# MainControl20V032.net
KiCad netlist of a schematic drawn in Altium Designer
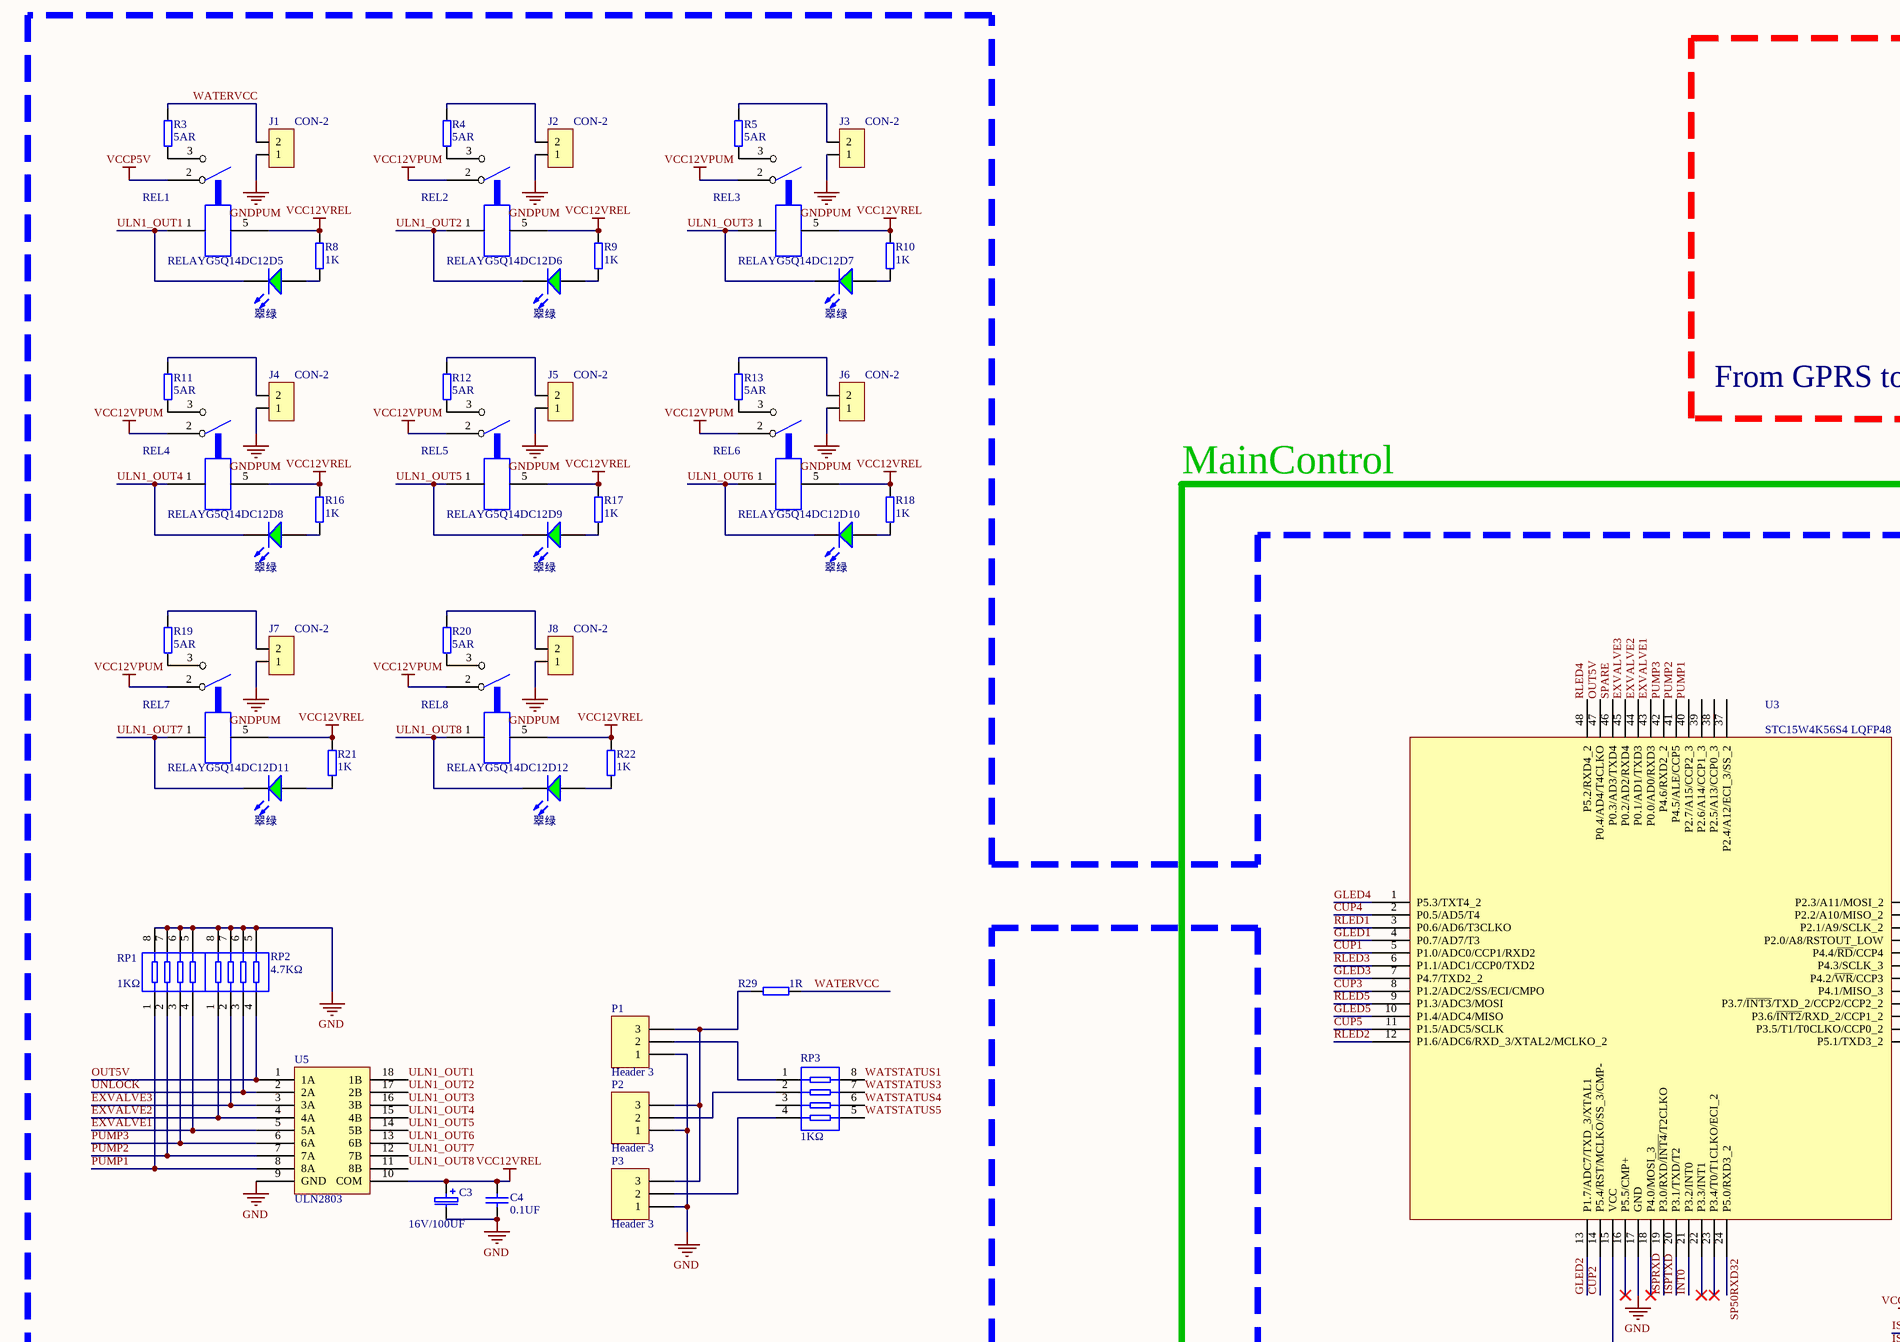
[diagram p0: MainControl20V032.SchDoc, top left]
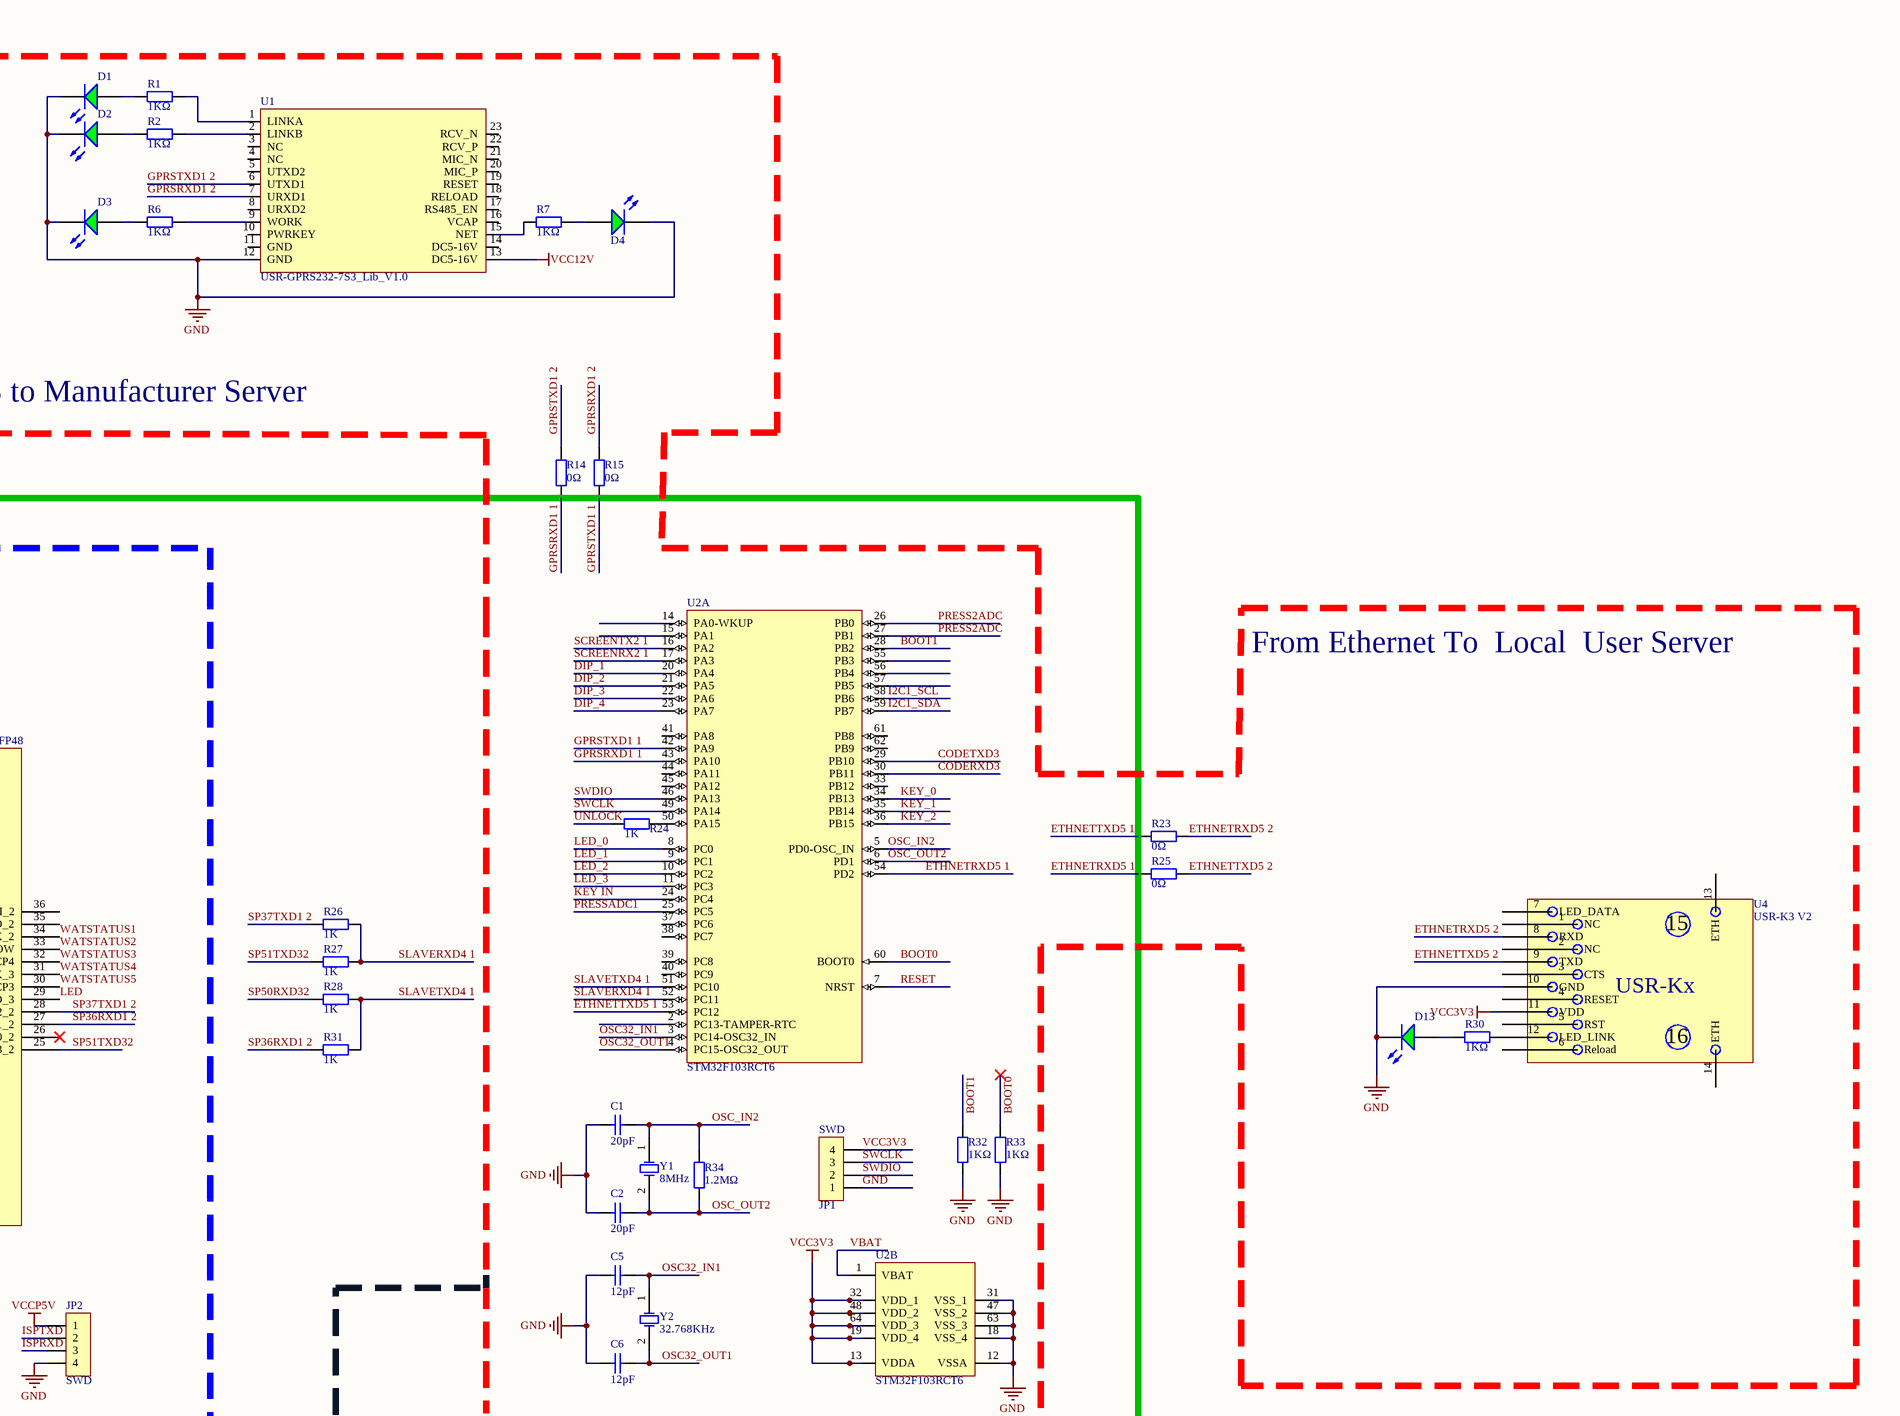
[diagram p1: MainControl20V032.SchDoc, top right]
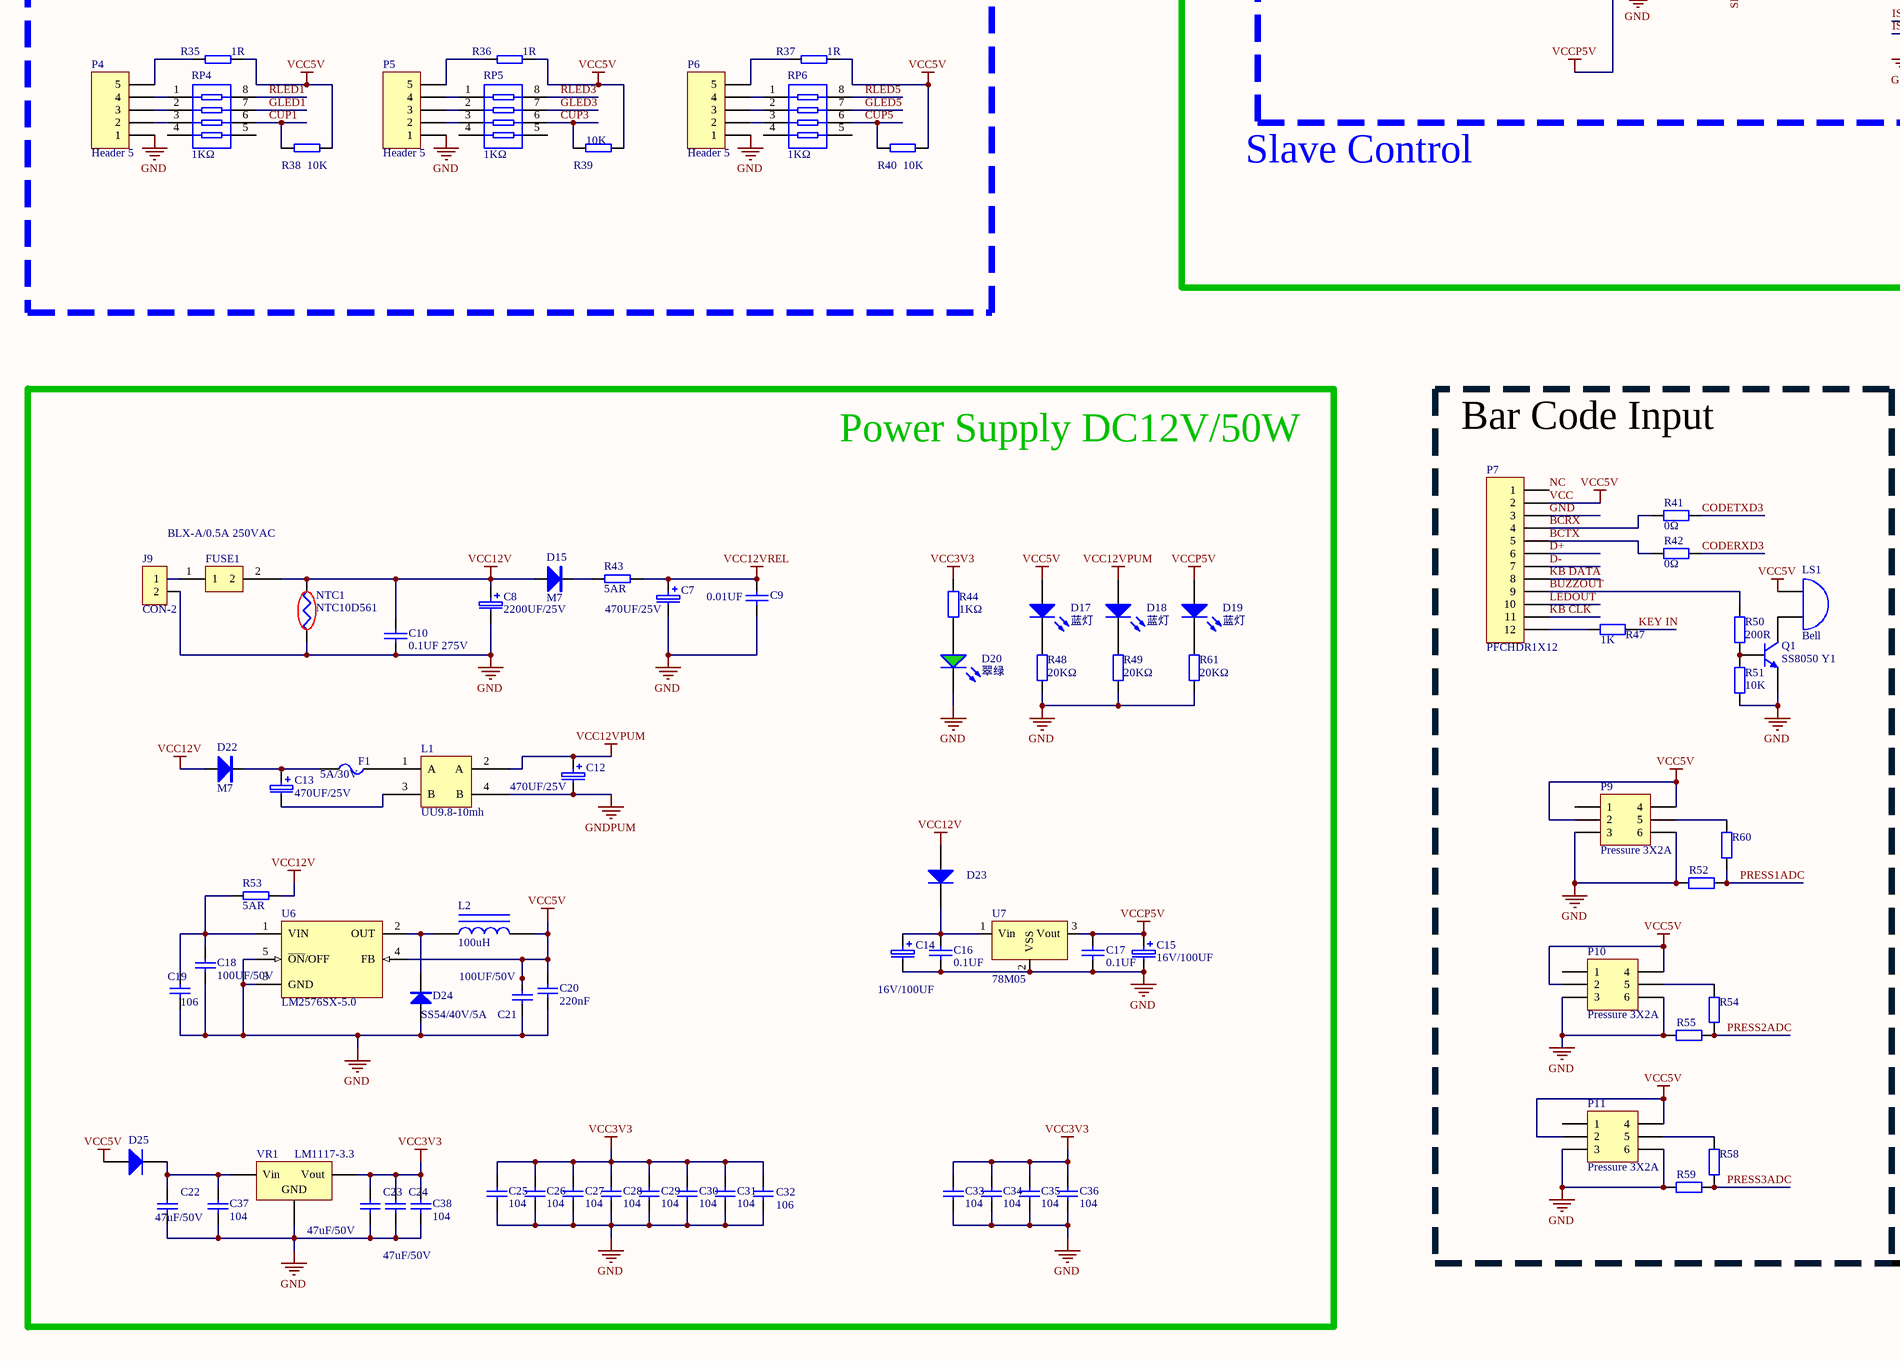
[diagram p2: MainControl20V032.SchDoc, bottom left]
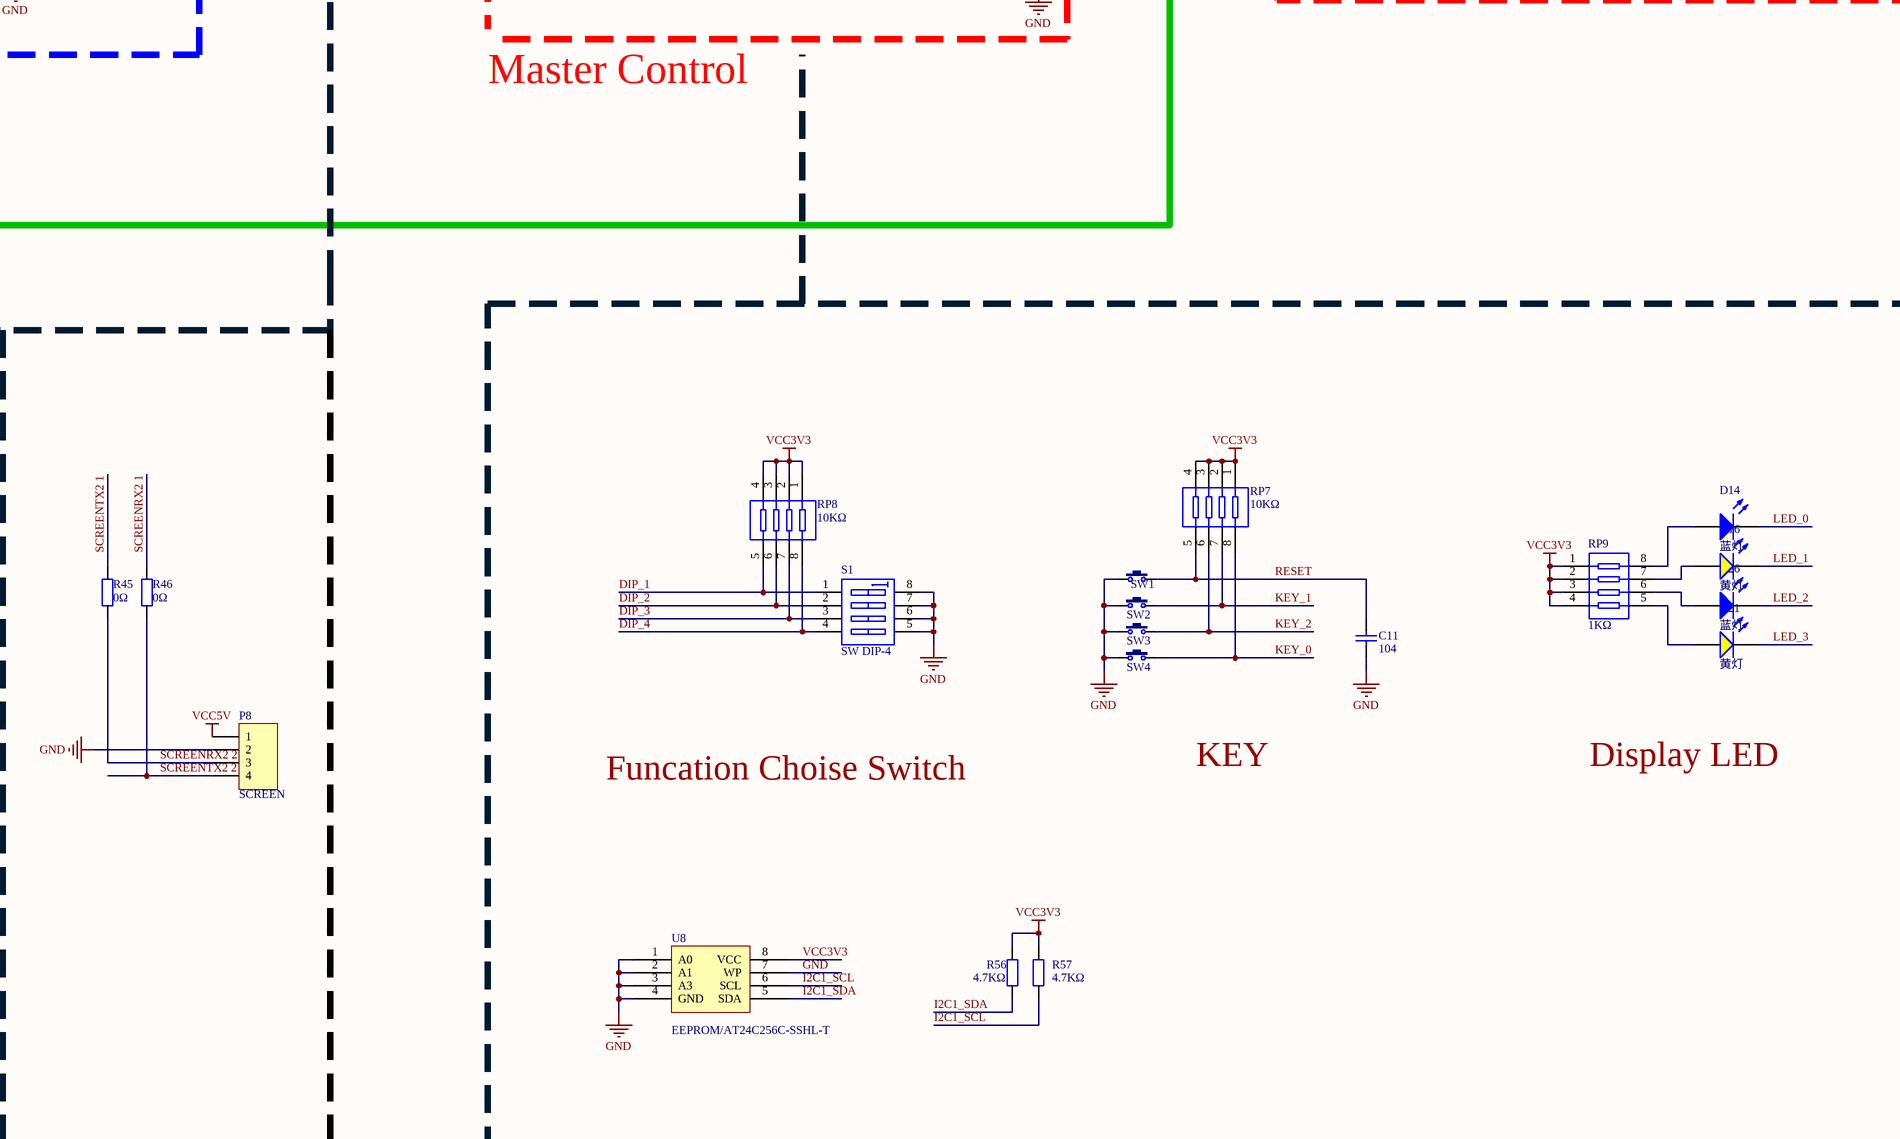
[diagram p3: MainControl20V032.SchDoc, bottom right]

(export (version "E")
  (design (tool "Eeschema 10.0.6"))
  (components
    (comp (ref "C1")
      (value "20pF")
      (footprint "1206_C")
      (description "贴片电容")
      (libsource (lib "Cap") (part "1206 470pF (471) 10% 50V"))
    )
    (comp (ref "C2")
      (value "20pF")
      (footprint "1206_C")
      (description "贴片电容")
      (libsource (lib "Cap") (part "1206 470pF (471) 10% 50V"))
    )
    (comp (ref "C3") (value "16V/100UF") (footprint "C0506") (libsource (lib "WegeV1") (part "EC")))
    (comp (ref "C4")
      (value "0.1UF")
      (footprint "C1206")
      (description "Cap")
      (libsource (lib "RX9910") (part "CAP-SMD"))
    )
    (comp (ref "C5")
      (value "12pF")
      (footprint "1206_C")
      (description "贴片电容")
      (libsource (lib "Cap") (part "1206 470pF (471) 10% 50V"))
    )
    (comp (ref "C6")
      (value "12pF")
      (footprint "1206_C")
      (description "贴片电容")
      (libsource (lib "Cap") (part "1206 470pF (471) 10% 50V"))
    )
    (comp (ref "C7") (value "470UF/25V") (footprint "C1020") (libsource (lib "WegeV1") (part "EC")))
    (comp (ref "C8") (value "2200UF/25V") (footprint "C1020") (libsource (lib "WegeV1") (part "EC")))
    (comp (ref "C9") (value "0.01UF") (footprint "C1206") (libsource (lib "WegeV1") (part "CAP")))
    (comp (ref "C10")
      (value "0.1UF 275V")
      (footprint "C1206")
      (description "安规电容 X2 275V 0.1uF 100nF 104K 脚距10mm")
      (libsource (lib "WegeV1") (part "CAP-X"))
    )
    (comp (ref "C11")
      (value "104")
      (footprint "1206_C")
      (description "贴片电容")
      (libsource (lib "Cap") (part "1206 100nF (104) 10% 50V"))
    )
    (comp (ref "C12") (value "470UF/25V") (footprint "C3618") (libsource (lib "WegeV1") (part "EC")))
    (comp (ref "C13") (value "470UF/25V") (footprint "C1020") (libsource (lib "WegeV1") (part "EC")))
    (comp (ref "C14") (value "16V/100UF") (footprint "C0506") (libsource (lib "WegeV1") (part "EC")))
    (comp (ref "C15") (value "16V/100UF") (footprint "C0506") (libsource (lib "WegeV1") (part "EC")))
    (comp (ref "C16")
      (value "0.1UF")
      (footprint "C1206")
      (description "Cap")
      (libsource (lib "RX9910") (part "CAP-SMD"))
    )
    (comp (ref "C17")
      (value "0.1UF")
      (footprint "C1206")
      (description "Cap")
      (libsource (lib "RX9910") (part "CAP-SMD"))
    )
    (comp (ref "C18")
      (value "100UF/50V")
      (footprint "CT 10*8 - C")
      (description "贴片电容")
      (libsource (lib "Cap") (part "1206 100nF (104) 10% 50V"))
    )
    (comp (ref "C19")
      (value "106")
      (footprint "1206_C")
      (description "贴片电容")
      (libsource (lib "Cap") (part "1206 10uF (106) 10% 50V"))
    )
    (comp (ref "C20")
      (value "220nF")
      (footprint "1206_C")
      (description "贴片电容")
      (libsource (lib "Cap") (part "1206 220nF (224) 10% 50V"))
    )
    (comp (ref "C21")
      (value "100UF/50V")
      (footprint "CT 10*8 - C")
      (description "贴片电容")
      (libsource (lib "Cap") (part "1206 100nF (104) 10% 50V"))
    )
    (comp (ref "C22")
      (value "47uF/50V")
      (footprint "CM D(6.3*7.7)")
      (description "贴片电容")
      (libsource (lib "Cap") (part "1206 470nF (474) 10% 50V"))
    )
    (comp (ref "C23")
      (value "47uF/50V")
      (footprint "CM D(6.3*7.7)")
      (description "贴片电容")
      (libsource (lib "Cap") (part "1206 470nF (474) 10% 50V"))
    )
    (comp (ref "C24")
      (value "47uF/50V")
      (footprint "CM D(6.3*7.7)")
      (description "贴片电容")
      (libsource (lib "Cap") (part "1206 470nF (474) 10% 50V"))
    )
    (comp (ref "C25")
      (value "104")
      (footprint "1206_C")
      (description "贴片电容")
      (libsource (lib "Cap") (part "1206 100nF (104) 10% 50V"))
    )
    (comp (ref "C26")
      (value "104")
      (footprint "1206_C")
      (description "贴片电容")
      (libsource (lib "Cap") (part "1206 100nF (104) 10% 50V"))
    )
    (comp (ref "C27")
      (value "104")
      (footprint "1206_C")
      (description "贴片电容")
      (libsource (lib "Cap") (part "1206 100nF (104) 10% 50V"))
    )
    (comp (ref "C28")
      (value "104")
      (footprint "1206_C")
      (description "贴片电容")
      (libsource (lib "Cap") (part "1206 100nF (104) 10% 50V"))
    )
    (comp (ref "C29")
      (value "104")
      (footprint "1206_C")
      (description "贴片电容")
      (libsource (lib "Cap") (part "1206 100nF (104) 10% 50V"))
    )
    (comp (ref "C30")
      (value "104")
      (footprint "1206_C")
      (description "贴片电容")
      (libsource (lib "Cap") (part "1206 100nF (104) 10% 50V"))
    )
    (comp (ref "C31")
      (value "104")
      (footprint "1206_C")
      (description "贴片电容")
      (libsource (lib "Cap") (part "1206 100nF (104) 10% 50V"))
    )
    (comp (ref "C32")
      (value "106")
      (footprint "1206_C")
      (description "贴片电容")
      (libsource (lib "Cap") (part "1206 10uF (106) 10% 50V"))
    )
    (comp (ref "C33")
      (value "104")
      (footprint "1206_C")
      (description "贴片电容")
      (libsource (lib "Cap") (part "1206 100nF (104) 10% 50V"))
    )
    (comp (ref "C34")
      (value "104")
      (footprint "1206_C")
      (description "贴片电容")
      (libsource (lib "Cap") (part "1206 100nF (104) 10% 50V"))
    )
    (comp (ref "C35")
      (value "104")
      (footprint "1206_C")
      (description "贴片电容")
      (libsource (lib "Cap") (part "1206 100nF (104) 10% 50V"))
    )
    (comp (ref "C36")
      (value "104")
      (footprint "1206_C")
      (description "贴片电容")
      (libsource (lib "Cap") (part "1206 100nF (104) 10% 50V"))
    )
    (comp (ref "C37")
      (value "104")
      (footprint "1206_C")
      (description "贴片电容")
      (libsource (lib "Cap") (part "1206 100nF (104) 10% 50V"))
    )
    (comp (ref "C38")
      (value "104")
      (footprint "1206_C")
      (description "贴片电容")
      (libsource (lib "Cap") (part "1206 100nF (104) 10% 50V"))
    )
    (comp (ref "D1")
      (value "翠绿")
      (footprint "0805_LED_S1")
      (description "发光二极管")
      (libsource (lib "LED") (part "0805 翠绿"))
    )
    (comp (ref "D2")
      (value "翠绿")
      (footprint "0805_LED_S1")
      (description "发光二极管")
      (libsource (lib "LED") (part "0805 翠绿"))
    )
    (comp (ref "D3")
      (value "翠绿")
      (footprint "0805_LED_S1")
      (description "发光二极管")
      (libsource (lib "LED") (part "0805 翠绿"))
    )
    (comp (ref "D4")
      (value "翠绿")
      (footprint "0805_LED_S1")
      (description "发光二极管")
      (libsource (lib "LED") (part "0805 翠绿"))
    )
    (comp (ref "D5")
      (value "翠绿")
      (footprint "0805_LED_S1")
      (description "发光二极管")
      (libsource (lib "LED") (part "0805 翠绿"))
    )
    (comp (ref "D6")
      (value "翠绿")
      (footprint "0805_LED_S1")
      (description "发光二极管")
      (libsource (lib "LED") (part "0805 翠绿"))
    )
    (comp (ref "D7")
      (value "翠绿")
      (footprint "0805_LED_S1")
      (description "发光二极管")
      (libsource (lib "LED") (part "0805 翠绿"))
    )
    (comp (ref "D8")
      (value "翠绿")
      (footprint "0805_LED_S1")
      (description "发光二极管")
      (libsource (lib "LED") (part "0805 翠绿"))
    )
    (comp (ref "D9")
      (value "翠绿")
      (footprint "0805_LED_S1")
      (description "发光二极管")
      (libsource (lib "LED") (part "0805 翠绿"))
    )
    (comp (ref "D10")
      (value "翠绿")
      (footprint "0805_LED_S1")
      (description "发光二极管")
      (libsource (lib "LED") (part "0805 翠绿"))
    )
    (comp (ref "D11")
      (value "翠绿")
      (footprint "0805_LED_S1")
      (description "发光二极管")
      (libsource (lib "LED") (part "0805 翠绿"))
    )
    (comp (ref "D12")
      (value "翠绿")
      (footprint "0805_LED_S1")
      (description "发光二极管")
      (libsource (lib "LED") (part "0805 翠绿"))
    )
    (comp (ref "D13")
      (value "翠绿")
      (footprint "0805_LED_S1")
      (description "发光二极管")
      (libsource (lib "LED") (part "0805 翠绿"))
    )
    (comp (ref "D14")
      (value "蓝灯")
      (footprint "0805_LED_S1")
      (description "发光二极管")
      (libsource (lib "LED") (part "0805 蓝灯"))
    )
    (comp (ref "D15") (value "M7") (footprint "DO-41") (libsource (lib "WegeV1") (part "M7")))
    (comp (ref "D16")
      (value "黄灯")
      (footprint "0805_LED_S1")
      (description "发光二极管")
      (libsource (lib "LED") (part "0805 黄灯"))
    )
    (comp (ref "D17")
      (value "蓝灯")
      (footprint "0805_LED_S1")
      (description "发光二极管")
      (libsource (lib "LED") (part "0805 蓝灯"))
    )
    (comp (ref "D18")
      (value "蓝灯")
      (footprint "0805_LED_S1")
      (description "发光二极管")
      (libsource (lib "LED") (part "0805 蓝灯"))
    )
    (comp (ref "D19")
      (value "蓝灯")
      (footprint "0805_LED_S1")
      (description "发光二极管")
      (libsource (lib "LED") (part "0805 蓝灯"))
    )
    (comp (ref "D20")
      (value "翠绿")
      (footprint "0805_LED_S1")
      (description "发光二极管")
      (libsource (lib "LED") (part "0805 翠绿"))
    )
    (comp (ref "D21")
      (value "黄灯")
      (footprint "0805_LED_S1")
      (description "发光二极管")
      (libsource (lib "LED") (part "0805 黄灯"))
    )
    (comp (ref "D22") (value "M7") (footprint "DO-41") (libsource (lib "WegeV1") (part "M7")))
    (comp (ref "D23")
      (value "LL4148 LL-34 1206")
      (footprint "LL-34")
      (description "开关二极管")
      (libsource (lib "Diode") (part "LL-34 LL4148 LL-34 1206"))
    )
    (comp (ref "D24")
      (value "SS54/40V/5A")
      (footprint "SMC(DO-214AB)_S1")
      (description "肖特基二极管")
      (fields (field (name "版权归属") "源创客"))
      (libsource (lib "8.1   - 二极管-整流桥") (part "1N5819"))
    )
    (comp (ref "D25")
      (value "LL4148 LL-34 1206")
      (footprint "LL-34")
      (description "开关二极管")
      (libsource (lib "Diode") (part "LL-34 LL4148 LL-34 1206"))
    )
    (comp (ref "D26")
      (value "蓝灯")
      (footprint "0805_LED_S1")
      (description "发光二极管")
      (libsource (lib "LED") (part "0805 蓝灯"))
    )
    (comp (ref "F1")
      (value "5A/30V")
      (footprint "RL30-500")
      (description "贴片保险丝")
      (fields (field (name "版权归属") "源创客"))
      (libsource (lib "10.1 - 保险丝-晶振") (part "FU"))
    )
    (comp (ref "FUSE1")
      (value "BLX-A/0.5A 250VAC")
      (footprint "NTC-10D")
      (libsource (lib "WegeV1") (part "BLX-A"))
    )
    (comp (ref "J1") (value "CON-2") (footprint "F396P2-1") (libsource (lib "WegeV1") (part "CON-2")))
    (comp (ref "J2") (value "CON-2") (footprint "F396P2-1") (libsource (lib "WegeV1") (part "CON-2")))
    (comp (ref "J3") (value "CON-2") (footprint "F396P2-1") (libsource (lib "WegeV1") (part "CON-2")))
    (comp (ref "J4") (value "CON-2") (footprint "F396P2-1") (libsource (lib "WegeV1") (part "CON-2")))
    (comp (ref "J5") (value "CON-2") (footprint "F396P2-1") (libsource (lib "WegeV1") (part "CON-2")))
    (comp (ref "J6") (value "CON-2") (footprint "F396P2-1") (libsource (lib "WegeV1") (part "CON-2")))
    (comp (ref "J7") (value "CON-2") (footprint "F396P2-1") (libsource (lib "WegeV1") (part "CON-2")))
    (comp (ref "J8") (value "CON-2") (footprint "F396P2-1") (libsource (lib "WegeV1") (part "CON-2")))
    (comp (ref "J9") (value "CON-2") (footprint "F396P2-1") (libsource (lib "") (part "CON-2_1")))
    (comp (ref "JP1")
      (value "SWD")
      (footprint "HDR2.54-M-LI-4P")
      (description "4P接插件")
      (fields (field (name "版权归属") "源创客"))
      (libsource (lib "4.5   - 接插件-脚距2.54") (part "Header 4"))
    )
    (comp (ref "JP2")
      (value "SWD")
      (footprint "HDR2.54-M-LI-4P")
      (description "4P接插件")
      (fields (field (name "版权归属") "源创客"))
      (libsource (lib "") (part "Header 4_1"))
    )
    (comp (ref "L1") (value "UU9.8-10mh") (footprint "TRANS") (libsource (lib "WegeV1") (part "INL-9.8MM")))
    (comp (ref "L2")
      (value "100uH")
      (footprint "H4.7UH")
      (description "贴片电感")
      (libsource (lib "IUD") (part "1206 10uH 10%"))
    )
    (comp (ref "LS1")
      (value "Bell")
      (footprint "PIN2")
      (description "Electrical Bell")
      (fields (field (name "PUBLISHER") "Altium Limited"))
      (libsource (lib "Miscellaneous Devices") (part "Bell"))
    )
    (comp (ref "NTC1") (value "NTC10D561") (footprint "NTC-10D") (libsource (lib "WegeV1") (part "NTC")))
    (comp (ref "P1")
      (value "Header 3")
      (footprint "HDR1X3")
      (description "Header, 3-Pin")
      (fields (field (name "PUBLISHER") "Altium Limited"))
      (libsource (lib "Miscellaneous Connectors") (part "Header 3"))
    )
    (comp (ref "P2")
      (value "Header 3")
      (footprint "HDR1X3")
      (description "Header, 3-Pin")
      (fields (field (name "PUBLISHER") "Altium Limited"))
      (libsource (lib "Miscellaneous Connectors") (part "Header 3"))
    )
    (comp (ref "P3")
      (value "Header 3")
      (footprint "HDR1X3")
      (description "Header, 3-Pin")
      (fields (field (name "PUBLISHER") "Altium Limited"))
      (libsource (lib "Miscellaneous Connectors") (part "Header 3"))
    )
    (comp (ref "P4")
      (value "Header 5")
      (footprint "HDR1X5")
      (description "Header, 5-Pin")
      (fields (field (name "PUBLISHER") "Altium Limited"))
      (libsource (lib "Miscellaneous Connectors") (part "Header 5"))
    )
    (comp (ref "P5")
      (value "Header 5")
      (footprint "HDR1X5")
      (description "Header, 5-Pin")
      (fields (field (name "PUBLISHER") "Altium Limited"))
      (libsource (lib "Miscellaneous Connectors") (part "Header 5"))
    )
    (comp (ref "P6")
      (value "Header 5")
      (footprint "HDR1X5")
      (description "Header, 5-Pin")
      (fields (field (name "PUBLISHER") "Altium Limited"))
      (libsource (lib "Miscellaneous Connectors") (part "Header 5"))
    )
    (comp (ref "P7")
      (value "PFCHDR1X12")
      (footprint "MHDR1X12")
      (description "Header, 12-Pin")
      (fields (field (name "PUBLISHER") "Altium Limited"))
      (libsource (lib "Miscellaneous Connectors") (part "MHDR1X12"))
    )
    (comp (ref "P8")
      (value "SCREEN")
      (footprint "MHDR1X4")
      (description "Header, 4-Pin")
      (fields (field (name "PUBLISHER") "Altium Limited"))
      (libsource (lib "Miscellaneous Connectors") (part "MHDR1X4"))
    )
    (comp (ref "P9")
      (value "Pressure 3X2A")
      (footprint "HDR2X3_CEN")
      (description "Header, 3-Pin, Dual row")
      (fields (field (name "PUBLISHER") "Altium Limited"))
      (libsource (lib "Miscellaneous Connectors") (part "Header 3X2A"))
    )
    (comp (ref "P10")
      (value "Pressure 3X2A")
      (footprint "HDR2X3_CEN")
      (description "Header, 3-Pin, Dual row")
      (fields (field (name "PUBLISHER") "Altium Limited"))
      (libsource (lib "Miscellaneous Connectors") (part "Header 3X2A"))
    )
    (comp (ref "P11")
      (value "Pressure 3X2A")
      (footprint "HDR2X3_CEN")
      (description "Header, 3-Pin, Dual row")
      (fields (field (name "PUBLISHER") "Altium Limited"))
      (libsource (lib "Miscellaneous Connectors") (part "Header 3X2A"))
    )
    (comp (ref "Q1")
      (value "SS8050 Y1")
      (footprint "SOT-23(SOT-23-3)")
      (description "三极管")
      (libsource (lib "Transistor_NPN") (part "SOT-23 SS8050 Y1"))
    )
    (comp (ref "R1")
      (value "1KΩ")
      (footprint "1206_R")
      (description "贴片电阻")
      (libsource (lib "") (part "1206 1KΩ (1001) 1%_2"))
    )
    (comp (ref "R2")
      (value "1KΩ")
      (footprint "1206_R")
      (description "贴片电阻")
      (libsource (lib "") (part "1206 1KΩ (1001) 1%_2"))
    )
    (comp (ref "R3")
      (value "5AR")
      (footprint "C1206")
      (description "SMD")
      (libsource (lib "RX9910") (part "RES-SMD"))
    )
    (comp (ref "R4")
      (value "5AR")
      (footprint "C1206")
      (description "SMD")
      (libsource (lib "RX9910") (part "RES-SMD"))
    )
    (comp (ref "R5")
      (value "5AR")
      (footprint "C1206")
      (description "SMD")
      (libsource (lib "RX9910") (part "RES-SMD"))
    )
    (comp (ref "R6")
      (value "1KΩ")
      (footprint "1206_R")
      (description "贴片电阻")
      (libsource (lib "") (part "1206 1KΩ (1001) 1%_2"))
    )
    (comp (ref "R7")
      (value "1KΩ")
      (footprint "1206_R")
      (description "贴片电阻")
      (libsource (lib "") (part "1206 1KΩ (1001) 1%_3"))
    )
    (comp (ref "R8") (value "1K") (footprint "C1206") (libsource (lib "WegeV1") (part "RES")))
    (comp (ref "R9") (value "1K") (footprint "C1206") (libsource (lib "WegeV1") (part "RES")))
    (comp (ref "R10") (value "1K") (footprint "C1206") (libsource (lib "WegeV1") (part "RES")))
    (comp (ref "R11")
      (value "5AR")
      (footprint "C1206")
      (description "SMD")
      (libsource (lib "RX9910") (part "RES-SMD"))
    )
    (comp (ref "R12")
      (value "5AR")
      (footprint "C1206")
      (description "SMD")
      (libsource (lib "RX9910") (part "RES-SMD"))
    )
    (comp (ref "R13")
      (value "5AR")
      (footprint "C1206")
      (description "SMD")
      (libsource (lib "RX9910") (part "RES-SMD"))
    )
    (comp (ref "R14")
      (value "0Ω")
      (footprint "1206_R")
      (description "贴片电阻")
      (libsource (lib "") (part "1206 0Ω (0R0) 1%_1"))
    )
    (comp (ref "R15")
      (value "0Ω")
      (footprint "1206_R")
      (description "贴片电阻")
      (libsource (lib "") (part "1206 0Ω (0R0) 1%_1"))
    )
    (comp (ref "R16") (value "1K") (footprint "C1206") (libsource (lib "WegeV1") (part "RES")))
    (comp (ref "R17") (value "1K") (footprint "C1206") (libsource (lib "WegeV1") (part "RES")))
    (comp (ref "R18") (value "1K") (footprint "C1206") (libsource (lib "WegeV1") (part "RES")))
    (comp (ref "R19")
      (value "5AR")
      (footprint "C1206")
      (description "SMD")
      (libsource (lib "RX9910") (part "RES-SMD"))
    )
    (comp (ref "R20")
      (value "5AR")
      (footprint "C1206")
      (description "SMD")
      (libsource (lib "RX9910") (part "RES-SMD"))
    )
    (comp (ref "R21") (value "1K") (footprint "C1206") (libsource (lib "WegeV1") (part "RES")))
    (comp (ref "R22") (value "1K") (footprint "C1206") (libsource (lib "WegeV1") (part "RES")))
    (comp (ref "R23")
      (value "0Ω")
      (footprint "1206_R")
      (description "贴片电阻")
      (libsource (lib "RES") (part "1206 0Ω (0R0) 1%"))
    )
    (comp (ref "R24")
      (value "1K")
      (footprint "1206_R")
      (description "贴片电阻")
      (libsource (lib "RES") (part "1206 0Ω (0R0) 1%"))
    )
    (comp (ref "R25")
      (value "0Ω")
      (footprint "1206_R")
      (description "贴片电阻")
      (libsource (lib "RES") (part "1206 0Ω (0R0) 1%"))
    )
    (comp (ref "R26")
      (value "1K")
      (footprint "1206_R")
      (description "贴片电阻")
      (libsource (lib "RES") (part "1206 0Ω (0R0) 1%"))
    )
    (comp (ref "R27")
      (value "1K")
      (footprint "1206_R")
      (description "贴片电阻")
      (libsource (lib "RES") (part "1206 0Ω (0R0) 1%"))
    )
    (comp (ref "R28")
      (value "1K")
      (footprint "1206_R")
      (description "贴片电阻")
      (libsource (lib "RES") (part "1206 0Ω (0R0) 1%"))
    )
    (comp (ref "R29") (value "1R") (footprint "C1206") (libsource (lib "WegeV1") (part "RES")))
    (comp (ref "R30")
      (value "1KΩ")
      (footprint "1206_R")
      (description "贴片电阻")
      (libsource (lib "") (part "1206 1KΩ (1001) 1%_2"))
    )
    (comp (ref "R31")
      (value "1K")
      (footprint "1206_R")
      (description "贴片电阻")
      (libsource (lib "RES") (part "1206 0Ω (0R0) 1%"))
    )
    (comp (ref "R32")
      (value "1KΩ")
      (footprint "1206_R")
      (description "贴片电阻")
      (libsource (lib "") (part "1206 1KΩ (1001) 1%_1"))
    )
    (comp (ref "R33")
      (value "1KΩ")
      (footprint "1206_R")
      (description "贴片电阻")
      (libsource (lib "") (part "1206 1KΩ (1001) 1%_1"))
    )
    (comp (ref "R34")
      (value "1.2MΩ")
      (footprint "1206_R")
      (description "贴片电阻")
      (libsource (lib "RES") (part "1206 1.2MΩ (1204) 1%"))
    )
    (comp (ref "R35") (value "1R") (footprint "C1206") (libsource (lib "WegeV1") (part "RES")))
    (comp (ref "R36") (value "1R") (footprint "C1206") (libsource (lib "WegeV1") (part "RES")))
    (comp (ref "R37") (value "1R") (footprint "C1206") (libsource (lib "WegeV1") (part "RES")))
    (comp (ref "R38") (value "10K") (footprint "C1206") (libsource (lib "WegeV1") (part "RES")))
    (comp (ref "R39") (value "10K") (footprint "C1206") (libsource (lib "WegeV1") (part "RES")))
    (comp (ref "R40") (value "10K") (footprint "C1206") (libsource (lib "WegeV1") (part "RES")))
    (comp (ref "R41")
      (value "0Ω")
      (footprint "1206_R")
      (description "贴片电阻")
      (libsource (lib "RES") (part "1206 0Ω (0R0) 1%"))
    )
    (comp (ref "R42")
      (value "0Ω")
      (footprint "1206_R")
      (description "贴片电阻")
      (libsource (lib "RES") (part "1206 0Ω (0R0) 1%"))
    )
    (comp (ref "R43")
      (value "5AR")
      (footprint "C1206")
      (description "SMD")
      (libsource (lib "RX9910") (part "RES-SMD"))
    )
    (comp (ref "R44")
      (value "1KΩ")
      (footprint "1206_R")
      (description "贴片电阻")
      (libsource (lib "") (part "1206 1KΩ (1001) 1%_1"))
    )
    (comp (ref "R45")
      (value "0Ω")
      (footprint "1206_R")
      (description "贴片电阻")
      (libsource (lib "") (part "1206 0Ω (0R0) 1%_1"))
    )
    (comp (ref "R46")
      (value "0Ω")
      (footprint "1206_R")
      (description "贴片电阻")
      (libsource (lib "") (part "1206 0Ω (0R0) 1%_1"))
    )
    (comp (ref "R47")
      (value "1K")
      (footprint "1206_R")
      (description "贴片电阻")
      (libsource (lib "RES") (part "1206 0Ω (0R0) 1%"))
    )
    (comp (ref "R48")
      (value "20KΩ")
      (footprint "1206_R")
      (description "贴片电阻")
      (libsource (lib "RES") (part "1206 1KΩ (1001) 1%"))
    )
    (comp (ref "R49")
      (value "20KΩ")
      (footprint "1206_R")
      (description "贴片电阻")
      (libsource (lib "RES") (part "1206 1KΩ (1001) 1%"))
    )
    (comp (ref "R50")
      (value "200R")
      (footprint "1206_R")
      (description "贴片电阻")
      (libsource (lib "") (part "1206 0Ω (0R0) 1%_1"))
    )
    (comp (ref "R51")
      (value "10K")
      (footprint "1206_R")
      (description "贴片电阻")
      (libsource (lib "") (part "1206 0Ω (0R0) 1%_1"))
    )
    (comp (ref "R52")
      (value "91KΩ (9102) ±1%")
      (footprint "0805_R")
      (description "贴片电阻")
      (libsource (lib "RES") (part "0805 91KΩ (9102) 1%"))
    )
    (comp (ref "R53")
      (value "5AR")
      (footprint "C1206")
      (description "SMD")
      (libsource (lib "RX9910") (part "RES-SMD"))
    )
    (comp (ref "R54")
      (value "68KΩ (6802) ±1%")
      (footprint "0805_R")
      (description "贴片电阻")
      (libsource (lib "RES") (part "0805 68KΩ (6802) 1%"))
    )
    (comp (ref "R55")
      (value "91KΩ (9102) ±1%")
      (footprint "0805_R")
      (description "贴片电阻")
      (libsource (lib "RES") (part "0805 91KΩ (9102) 1%"))
    )
    (comp (ref "R56")
      (value "4.7KΩ")
      (footprint "1206_R")
      (description "贴片电阻")
      (libsource (lib "") (part "1206 1KΩ (1001) 1%_1"))
    )
    (comp (ref "R57")
      (value "4.7KΩ")
      (footprint "1206_R")
      (description "贴片电阻")
      (libsource (lib "") (part "1206 1KΩ (1001) 1%_1"))
    )
    (comp (ref "R58")
      (value "68KΩ (6802) ±1%")
      (footprint "0805_R")
      (description "贴片电阻")
      (libsource (lib "RES") (part "0805 68KΩ (6802) 1%"))
    )
    (comp (ref "R59")
      (value "91KΩ (9102) ±1%")
      (footprint "0805_R")
      (description "贴片电阻")
      (libsource (lib "RES") (part "0805 91KΩ (9102) 1%"))
    )
    (comp (ref "R60")
      (value "68KΩ (6802) ±1%")
      (footprint "0805_R")
      (description "贴片电阻")
      (libsource (lib "RES") (part "0805 68KΩ (6802) 1%"))
    )
    (comp (ref "R61")
      (value "20KΩ")
      (footprint "1206_R")
      (description "贴片电阻")
      (libsource (lib "RES") (part "1206 1KΩ (1001) 1%"))
    )
    (comp (ref "REL1")
      (value "RELAYG5Q14DC12")
      (footprint "RELAY-HF3FF1Z")
      (libsource (lib "MainControl20V01") (part "RELAYG5Q14DC12"))
    )
    (comp (ref "REL2")
      (value "RELAYG5Q14DC12")
      (footprint "RELAY-HF3FF1Z")
      (libsource (lib "MainControl20V01") (part "RELAYG5Q14DC12"))
    )
    (comp (ref "REL3")
      (value "RELAYG5Q14DC12")
      (footprint "RELAY-HF3FF1Z")
      (libsource (lib "MainControl20V01") (part "RELAYG5Q14DC12"))
    )
    (comp (ref "REL4")
      (value "RELAYG5Q14DC12")
      (footprint "RELAY-HF3FF1Z")
      (libsource (lib "MainControl20V01") (part "RELAYG5Q14DC12"))
    )
    (comp (ref "REL5")
      (value "RELAYG5Q14DC12")
      (footprint "RELAY-HF3FF1Z")
      (libsource (lib "MainControl20V01") (part "RELAYG5Q14DC12"))
    )
    (comp (ref "REL6")
      (value "RELAYG5Q14DC12")
      (footprint "RELAY-HF3FF1Z")
      (libsource (lib "MainControl20V01") (part "RELAYG5Q14DC12"))
    )
    (comp (ref "REL7")
      (value "RELAYG5Q14DC12")
      (footprint "RELAY-HF3FF1Z")
      (libsource (lib "MainControl20V01") (part "RELAYG5Q14DC12"))
    )
    (comp (ref "REL8")
      (value "RELAYG5Q14DC12")
      (footprint "RELAY-HF3FF1Z")
      (libsource (lib "MainControl20V01") (part "RELAYG5Q14DC12"))
    )
    (comp (ref "RP1")
      (value "1KΩ")
      (footprint "0603_Rx4")
      (description "贴片排阻")
      (libsource (lib "RES") (part "0603*4  1KΩ (102) 5%"))
    )
    (comp (ref "RP2")
      (value "4.7KΩ")
      (footprint "0603_Rx4")
      (description "贴片排阻")
      (libsource (lib "RES") (part "0603*4  1KΩ (102) 5%"))
    )
    (comp (ref "RP3")
      (value "1KΩ")
      (footprint "0603_Rx4")
      (description "贴片排阻")
      (libsource (lib "RES") (part "0603*4  1KΩ (102) 5%"))
    )
    (comp (ref "RP4")
      (value "1KΩ")
      (footprint "0603_Rx4")
      (description "贴片排阻")
      (libsource (lib "RES") (part "0603*4  1KΩ (102) 5%"))
    )
    (comp (ref "RP5")
      (value "1KΩ")
      (footprint "0603_Rx4")
      (description "贴片排阻")
      (libsource (lib "RES") (part "0603*4  1KΩ (102) 5%"))
    )
    (comp (ref "RP6")
      (value "1KΩ")
      (footprint "0603_Rx4")
      (description "贴片排阻")
      (libsource (lib "RES") (part "0603*4  1KΩ (102) 5%"))
    )
    (comp (ref "RP7")
      (value "10KΩ")
      (footprint "0603_Rx4")
      (description "贴片排阻")
      (libsource (lib "RES") (part "0603*4  1KΩ (102) 5%"))
    )
    (comp (ref "RP8")
      (value "10KΩ")
      (footprint "0603_Rx4")
      (description "贴片排阻")
      (libsource (lib "RES") (part "0603*4  1KΩ (102) 5%"))
    )
    (comp (ref "RP9")
      (value "1KΩ")
      (footprint "0603_Rx4")
      (description "贴片排阻")
      (libsource (lib "RES") (part "0603*4  1KΩ (102) 5%"))
    )
    (comp (ref "S1")
      (value "SW DIP-4")
      (footprint "SO8_N")
      (description "DIP Switch, 4 Position, SPST")
      (fields (field (name "PUBLISHER") "Altium Limited"))
      (libsource (lib "Miscellaneous Devices") (part "SW DIP-4"))
    )
    (comp (ref "SW1")
      (value "3x6x5")
      (footprint "TSW SMD-3*6*2.5")
      (description "3x6轻触开关")
      (fields (field (name "版权归属") "源创客"))
      (libsource (lib "5.1   - 按键-开关") (part "TSW 3x6"))
    )
    (comp (ref "SW2")
      (value "3x6x5")
      (footprint "TSW SMD-3*6*2.5")
      (description "3x6轻触开关")
      (fields (field (name "版权归属") "源创客"))
      (libsource (lib "5.1   - 按键-开关") (part "TSW 3x6"))
    )
    (comp (ref "SW3")
      (value "3x6x5")
      (footprint "TSW SMD-3*6*2.5")
      (description "3x6轻触开关")
      (fields (field (name "版权归属") "源创客"))
      (libsource (lib "5.1   - 按键-开关") (part "TSW 3x6"))
    )
    (comp (ref "SW4")
      (value "3x6x5")
      (footprint "TSW SMD-3*6*2.5")
      (description "3x6轻触开关")
      (fields (field (name "版权归属") "源创客"))
      (libsource (lib "5.1   - 按键-开关") (part "TSW 3x6"))
    )
    (comp (ref "U1")
      (value "USR-GPRS232-7S3_Lib_V1.0")
      (libsource (lib "USR-GPRS232-7S3_Lib_V1.0") (part "USR-GPRS232-7S3_Lib_V1.0"))
    )
    (comp (ref "U2")
      (value "STM32F103RCT6")
      (footprint "LQFP-64_10x10x05P")
      (description "ARM")
      (libsource (lib "MCU") (part "STM32F103RCT6"))
    )
    (comp (ref "U3")
      (value "STC15W4K56S4 LQFP48")
      (footprint "LQFP48")
      (libsource (lib "WegeV1") (part "STC15W4K60S4 LQFP48"))
    )
    (comp (ref "U4") (value "USR-K3 V2") (libsource (lib "USR-Kx") (part "USR-K3 V2")))
    (comp (ref "U5") (value "ULN2803") (footprint "SOP18") (libsource (lib "WegeV1") (part "ULN2803")))
    (comp (ref "U6")
      (value "LM2576SX-5.0")
      (footprint "TO-263-5")
      (description "DC-DC芯片")
      (libsource (lib "Miscellaneous Devices LC") (part "LM2576SX-5.0_[C34465]"))
    )
    (comp (ref "U7") (value "78M05") (footprint "D-PAK") (libsource (lib "WegeV1") (part "78M05")))
    (comp (ref "U8")
      (value "EEPROM/AT24C256C-SSHL-T")
      (footprint "SOIC-8_150mil")
      (description "EEPROM")
      (libsource (lib "Miscellaneous Devices LC") (part "EEPROM/AT24C256C-SSHL-T_[C6482]"))
    )
    (comp (ref "VR1")
      (value "LM1117-3.3")
      (footprint "SOT-223")
      (description "低压差线性稳压(LDO)")
      (libsource (lib "LDO") (part "SOT-223 AMS1117-3.3"))
    )
    (comp (ref "Y1")
      (value "8MHz")
      (footprint "SMD-5032_2P")
      (description "贴片晶振")
      (libsource (lib "CrystalOscillator") (part "SMD-5032_2P 8MHz 20ppm 20pF"))
    )
    (comp (ref "Y2")
      (value "32.768KHz")
      (footprint "SMD-3215_2P FC - 135")
      (description "贴片晶振")
      (libsource (lib "CrystalOscillator") (part "SMD-3215_2P 32.768KHz 20ppm 12.5pF"))
    )
  )
  (nets
    (net (code "1") (name "/BCRX") (class "Default")
      (node (ref "P7") (pin "4") (pinfunction "4_4") (pintype "passive"))
      (node (ref "R41") (pin "1") (pinfunction "1_1") (pintype "passive"))
    )
    (net (code "2") (name "/BCTX") (class "Default")
      (node (ref "P7") (pin "5") (pinfunction "5_5") (pintype "passive"))
      (node (ref "R42") (pin "1") (pinfunction "1_1") (pintype "passive"))
    )
    (net (code "3") (name "/BOOT0") (class "Default")
      (node (ref "R33") (pin "2") (pinfunction "2_2") (pintype "passive"))
      (node (ref "U2") (pin "60") (pinfunction "BOOT0_60") (pintype "input"))
    )
    (net (code "4") (name "/BOOT1") (class "Default")
      (node (ref "R32") (pin "2") (pinfunction "2_2") (pintype "passive"))
      (node (ref "U2") (pin "28") (pinfunction "PB2_28") (pintype "bidirectional"))
    )
    (net (code "5") (name "/BUZZOUT") (class "Default")
      (node (ref "P7") (pin "9") (pinfunction "9_9") (pintype "passive"))
      (node (ref "R50") (pin "2") (pinfunction "2_2") (pintype "passive"))
    )
    (net (code "6") (name "/CODERXD3") (class "Default")
      (node (ref "R42") (pin "2") (pinfunction "2_2") (pintype "passive"))
      (node (ref "U2") (pin "30") (pinfunction "PB11_30") (pintype "bidirectional"))
    )
    (net (code "7") (name "/CODETXD3") (class "Default")
      (node (ref "R41") (pin "2") (pinfunction "2_2") (pintype "passive"))
      (node (ref "U2") (pin "29") (pinfunction "PB10_29") (pintype "bidirectional"))
    )
    (net (code "8") (name "/CUP1") (class "Default")
      (node (ref "R38") (pin "2") (pinfunction "2_2") (pintype "passive"))
      (node (ref "RP4") (pin "6") (pinfunction "6_6") (pintype "passive"))
      (node (ref "U3") (pin "5") (pinfunction "P1.0/ADC0/CCP1/RXD2_5") (pintype "passive"))
    )
    (net (code "9") (name "/CUP2") (class "Default")
      (node (ref "U3") (pin "14") (pinfunction "P5.4/RST/MCLKO/SS_3/CMP-_14") (pintype "passive"))
    )
    (net (code "10") (name "/CUP3") (class "Default")
      (node (ref "R39") (pin "2") (pinfunction "2_2") (pintype "passive"))
      (node (ref "RP5") (pin "6") (pinfunction "6_6") (pintype "passive"))
      (node (ref "U3") (pin "8") (pinfunction "P1.2/ADC2/SS/ECI/CMPO_8") (pintype "passive"))
    )
    (net (code "11") (name "/CUP4") (class "Default")
      (node (ref "U3") (pin "2") (pinfunction "P0.5/AD5/T4_2") (pintype "passive"))
    )
    (net (code "12") (name "/CUP5") (class "Default")
      (node (ref "R40") (pin "2") (pinfunction "2_2") (pintype "passive"))
      (node (ref "RP6") (pin "6") (pinfunction "6_6") (pintype "passive"))
      (node (ref "U3") (pin "11") (pinfunction "P1.5/ADC5/SCLK_11") (pintype "passive"))
    )
    (net (code "13") (name "/D+") (class "Default")
      (node (ref "P7") (pin "6") (pinfunction "6_6") (pintype "passive"))
    )
    (net (code "14") (name "/D-") (class "Default")
      (node (ref "P7") (pin "7") (pinfunction "7_7") (pintype "passive"))
    )
    (net (code "15") (name "/DIP_1") (class "Default")
      (node (ref "RP8") (pin "5") (pinfunction "5_5") (pintype "passive"))
      (node (ref "S1") (pin "1") (pinfunction "A1_1") (pintype "passive"))
      (node (ref "U2") (pin "20") (pinfunction "PA4_20") (pintype "bidirectional"))
    )
    (net (code "16") (name "/DIP_2") (class "Default")
      (node (ref "RP8") (pin "6") (pinfunction "6_6") (pintype "passive"))
      (node (ref "S1") (pin "2") (pinfunction "A2_2") (pintype "passive"))
      (node (ref "U2") (pin "21") (pinfunction "PA5_21") (pintype "bidirectional"))
    )
    (net (code "17") (name "/DIP_3") (class "Default")
      (node (ref "RP8") (pin "7") (pinfunction "7_7") (pintype "passive"))
      (node (ref "S1") (pin "3") (pinfunction "A3_3") (pintype "passive"))
      (node (ref "U2") (pin "22") (pinfunction "PA6_22") (pintype "bidirectional"))
    )
    (net (code "18") (name "/DIP_4") (class "Default")
      (node (ref "RP8") (pin "8") (pinfunction "8_8") (pintype "passive"))
      (node (ref "S1") (pin "4") (pinfunction "A4_4") (pintype "passive"))
      (node (ref "U2") (pin "23") (pinfunction "PA7_23") (pintype "bidirectional"))
    )
    (net (code "19") (name "/ETHNETRXD5 1") (class "Default")
      (node (ref "R25") (pin "1") (pinfunction "1_1") (pintype "passive"))
      (node (ref "U2") (pin "54") (pinfunction "PD2_54") (pintype "bidirectional"))
    )
    (net (code "20") (name "/ETHNETRXD5 2") (class "Default")
      (node (ref "R23") (pin "2") (pinfunction "2_2") (pintype "passive"))
      (node (ref "U4") (pin "8") (pinfunction "RXD_8") (pintype "passive"))
    )
    (net (code "21") (name "/ETHNETTXD5 1") (class "Default")
      (node (ref "R23") (pin "1") (pinfunction "1_1") (pintype "passive"))
      (node (ref "U2") (pin "53") (pinfunction "PC12_53") (pintype "bidirectional"))
    )
    (net (code "22") (name "/ETHNETTXD5 2") (class "Default")
      (node (ref "R25") (pin "2") (pinfunction "2_2") (pintype "passive"))
      (node (ref "U4") (pin "9") (pinfunction "TXD_9") (pintype "passive"))
    )
    (net (code "23") (name "/EXVALVE1") (class "Default")
      (node (ref "RP1") (pin "4") (pinfunction "4_4") (pintype "passive"))
      (node (ref "U3") (pin "43") (pinfunction "P0.0/AD0/RXD3_43") (pintype "passive"))
      (node (ref "U5") (pin "5") (pinfunction "5A_5") (pintype "passive"))
    )
    (net (code "24") (name "/EXVALVE2") (class "Default")
      (node (ref "RP2") (pin "1") (pinfunction "1_1") (pintype "passive"))
      (node (ref "U3") (pin "44") (pinfunction "P0.1/AD1/TXD3_44") (pintype "passive"))
      (node (ref "U5") (pin "4") (pinfunction "4A_4") (pintype "passive"))
    )
    (net (code "25") (name "/EXVALVE3") (class "Default")
      (node (ref "RP2") (pin "2") (pinfunction "2_2") (pintype "passive"))
      (node (ref "U3") (pin "45") (pinfunction "P0.2/AD2/RXD4_45") (pintype "passive"))
      (node (ref "U5") (pin "3") (pinfunction "3A_3") (pintype "passive"))
    )
    (net (code "26") (name "/GLED1") (class "Default")
      (node (ref "RP4") (pin "7") (pinfunction "7_7") (pintype "passive"))
      (node (ref "U3") (pin "4") (pinfunction "P0.7/AD7/T3_4") (pintype "passive"))
    )
    (net (code "27") (name "/GLED2") (class "Default")
      (node (ref "U3") (pin "13") (pinfunction "P1.7/ADC7/TXD_3/XTAL1_13") (pintype "passive"))
    )
    (net (code "28") (name "/GLED3") (class "Default")
      (node (ref "RP5") (pin "7") (pinfunction "7_7") (pintype "passive"))
      (node (ref "U3") (pin "7") (pinfunction "P4.7/TXD2_2_7") (pintype "passive"))
    )
    (net (code "29") (name "/GLED4") (class "Default")
      (node (ref "U3") (pin "1") (pinfunction "P5.3/TXT4_2_1") (pintype "passive"))
    )
    (net (code "30") (name "/GLED5") (class "Default")
      (node (ref "RP6") (pin "7") (pinfunction "7_7") (pintype "passive"))
      (node (ref "U3") (pin "10") (pinfunction "P1.4/ADC4/MISO_10") (pintype "passive"))
    )
    (net (code "31") (name "/GPRSRXD1 1") (class "Default")
      (node (ref "R14") (pin "1") (pinfunction "1_1") (pintype "passive"))
      (node (ref "U2") (pin "43") (pinfunction "PA10_43") (pintype "bidirectional"))
    )
    (net (code "32") (name "/GPRSRXD1 2") (class "Default")
      (node (ref "R15") (pin "2") (pinfunction "2_2") (pintype "passive"))
      (node (ref "U1") (pin "7") (pinfunction "URXD1_7") (pintype "passive"))
    )
    (net (code "33") (name "/GPRSTXD1 1") (class "Default")
      (node (ref "R15") (pin "1") (pinfunction "1_1") (pintype "passive"))
      (node (ref "U2") (pin "42") (pinfunction "PA9_42") (pintype "bidirectional"))
    )
    (net (code "34") (name "/GPRSTXD1 2") (class "Default")
      (node (ref "R14") (pin "2") (pinfunction "2_2") (pintype "passive"))
      (node (ref "U1") (pin "6") (pinfunction "UTXD1_6") (pintype "passive"))
    )
    (net (code "35") (name "/I2C1_SCL") (class "Default")
      (node (ref "R57") (pin "1") (pinfunction "1_1") (pintype "passive"))
      (node (ref "U2") (pin "58") (pinfunction "PB6_58") (pintype "bidirectional"))
      (node (ref "U8") (pin "6") (pinfunction "SCL_6") (pintype "passive"))
    )
    (net (code "36") (name "/I2C1_SDA") (class "Default")
      (node (ref "R56") (pin "1") (pinfunction "1_1") (pintype "passive"))
      (node (ref "U2") (pin "59") (pinfunction "PB7_59") (pintype "bidirectional"))
      (node (ref "U8") (pin "5") (pinfunction "SDA_5") (pintype "passive"))
    )
    (net (code "37") (name "/INT0") (class "Default")
      (node (ref "U3") (pin "21") (pinfunction "P3.2/INT0_21") (pintype "passive"))
    )
    (net (code "38") (name "/ISPRXD") (class "Default")
      (node (ref "JP2") (pin "3") (pinfunction "3_3") (pintype "passive"))
      (node (ref "U3") (pin "19") (pinfunction "P3.0/RXD/~{INT4}/T2CLKO_19") (pintype "passive"))
    )
    (net (code "39") (name "/ISPTXD") (class "Default")
      (node (ref "JP2") (pin "2") (pinfunction "2_2") (pintype "passive"))
      (node (ref "U3") (pin "20") (pinfunction "P3.1/TXD/T2_20") (pintype "passive"))
    )
    (net (code "40") (name "/KB CLK") (class "Default")
      (node (ref "P7") (pin "11") (pinfunction "11_11") (pintype "passive"))
    )
    (net (code "41") (name "/KB DATA") (class "Default")
      (node (ref "P7") (pin "8") (pinfunction "8_8") (pintype "passive"))
    )
    (net (code "42") (name "/KEY IN") (class "Default")
      (node (ref "R47") (pin "2") (pinfunction "2_2") (pintype "passive"))
      (node (ref "U2") (pin "24") (pinfunction "PC4_24") (pintype "bidirectional"))
    )
    (net (code "43") (name "/KEY_0") (class "Default")
      (node (ref "RP7") (pin "8") (pinfunction "8_8") (pintype "passive"))
      (node (ref "SW4") (pin "2") (pinfunction "2_2") (pintype "passive"))
      (node (ref "U2") (pin "34") (pinfunction "PB13_34") (pintype "bidirectional"))
    )
    (net (code "44") (name "/KEY_1") (class "Default")
      (node (ref "RP7") (pin "7") (pinfunction "7_7") (pintype "passive"))
      (node (ref "SW2") (pin "2") (pinfunction "2_2") (pintype "passive"))
      (node (ref "U2") (pin "35") (pinfunction "PB14_35") (pintype "bidirectional"))
    )
    (net (code "45") (name "/KEY_2") (class "Default")
      (node (ref "RP7") (pin "6") (pinfunction "6_6") (pintype "passive"))
      (node (ref "SW3") (pin "2") (pinfunction "2_2") (pintype "passive"))
      (node (ref "U2") (pin "36") (pinfunction "PB15_36") (pintype "bidirectional"))
    )
    (net (code "46") (name "/LED") (class "Default")
      (node (ref "U3") (pin "29") (pinfunction "P4.1/MISO_3_29") (pintype "passive"))
    )
    (net (code "47") (name "/LEDOUT") (class "Default")
      (node (ref "P7") (pin "10") (pinfunction "10_10") (pintype "passive"))
    )
    (net (code "48") (name "/LED_0") (class "Default")
      (node (ref "D14") (pin "K") (pinfunction "K_K") (pintype "passive"))
      (node (ref "U2") (pin "8") (pinfunction "PC0_8") (pintype "bidirectional"))
    )
    (net (code "49") (name "/LED_1") (class "Default")
      (node (ref "D16") (pin "K") (pinfunction "K_K") (pintype "passive"))
      (node (ref "U2") (pin "9") (pinfunction "PC1_9") (pintype "bidirectional"))
    )
    (net (code "50") (name "/LED_2") (class "Default")
      (node (ref "D26") (pin "K") (pinfunction "K_K") (pintype "passive"))
      (node (ref "U2") (pin "10") (pinfunction "PC2_10") (pintype "bidirectional"))
    )
    (net (code "51") (name "/LED_3") (class "Default")
      (node (ref "D21") (pin "K") (pinfunction "K_K") (pintype "passive"))
      (node (ref "U2") (pin "11") (pinfunction "PC3_11") (pintype "bidirectional"))
    )
    (net (code "52") (name "/NC") (class "Default")
      (node (ref "P7") (pin "1") (pinfunction "1_1") (pintype "passive"))
    )
    (net (code "53") (name "/OSC32_IN1") (class "Default")
      (node (ref "C5") (pin "2") (pinfunction "2_2") (pintype "passive"))
      (node (ref "U2") (pin "3") (pinfunction "PC14-OSC32_IN_3") (pintype "bidirectional"))
      (node (ref "Y2") (pin "1") (pinfunction "OSC1_1") (pintype "passive"))
    )
    (net (code "54") (name "/OSC32_OUT1") (class "Default")
      (node (ref "C6") (pin "2") (pinfunction "2_2") (pintype "passive"))
      (node (ref "U2") (pin "4") (pinfunction "PC15-OSC32_OUT_4") (pintype "bidirectional"))
      (node (ref "Y2") (pin "2") (pinfunction "OSC2_2") (pintype "passive"))
    )
    (net (code "55") (name "/OSC_IN2") (class "Default")
      (node (ref "C1") (pin "2") (pinfunction "2_2") (pintype "passive"))
      (node (ref "R34") (pin "2") (pinfunction "2_2") (pintype "passive"))
      (node (ref "U2") (pin "5") (pinfunction "PD0-OSC_IN_5") (pintype "bidirectional"))
      (node (ref "Y1") (pin "1") (pinfunction "OSC1_1") (pintype "passive"))
    )
    (net (code "56") (name "/OSC_OUT2") (class "Default")
      (node (ref "C2") (pin "2") (pinfunction "2_2") (pintype "passive"))
      (node (ref "R34") (pin "1") (pinfunction "1_1") (pintype "passive"))
      (node (ref "U2") (pin "6") (pinfunction "PD1_6") (pintype "bidirectional"))
      (node (ref "Y1") (pin "2") (pinfunction "OSC2_2") (pintype "passive"))
    )
    (net (code "57") (name "/OUT5V") (class "Default")
      (node (ref "RP2") (pin "4") (pinfunction "4_4") (pintype "passive"))
      (node (ref "U3") (pin "47") (pinfunction "P0.4/AD4/T4CLKO_47") (pintype "passive"))
      (node (ref "U5") (pin "1") (pinfunction "1A_1") (pintype "passive"))
    )
    (net (code "58") (name "/PRESS1ADC") (class "Default")
      (node (ref "R52") (pin "2") (pinfunction "2_2") (pintype "passive"))
      (node (ref "R60") (pin "1") (pinfunction "1_1") (pintype "passive"))
    )
    (net (code "59") (name "/PRESS2ADC") (class "Default")
      (node (ref "R54") (pin "1") (pinfunction "1_1") (pintype "passive"))
      (node (ref "R55") (pin "2") (pinfunction "2_2") (pintype "passive"))
      (node (ref "U2") (pin "26") (pinfunction "PB0_26") (pintype "bidirectional"))
      (node (ref "U2") (pin "27") (pinfunction "PB1_27") (pintype "bidirectional"))
    )
    (net (code "60") (name "/PRESS3ADC") (class "Default")
      (node (ref "R58") (pin "1") (pinfunction "1_1") (pintype "passive"))
      (node (ref "R59") (pin "2") (pinfunction "2_2") (pintype "passive"))
    )
    (net (code "61") (name "/PRESSADC1") (class "Default")
      (node (ref "U2") (pin "25") (pinfunction "PC5_25") (pintype "bidirectional"))
    )
    (net (code "62") (name "/PUMP1") (class "Default")
      (node (ref "RP1") (pin "1") (pinfunction "1_1") (pintype "passive"))
      (node (ref "U3") (pin "40") (pinfunction "P2.7/A15/CCP2_3_40") (pintype "passive"))
      (node (ref "U5") (pin "8") (pinfunction "8A_8") (pintype "passive"))
    )
    (net (code "63") (name "/PUMP2") (class "Default")
      (node (ref "RP1") (pin "2") (pinfunction "2_2") (pintype "passive"))
      (node (ref "U3") (pin "41") (pinfunction "P4.5/ALE/CCP5_41") (pintype "passive"))
      (node (ref "U5") (pin "7") (pinfunction "7A_7") (pintype "passive"))
    )
    (net (code "64") (name "/PUMP3") (class "Default")
      (node (ref "RP1") (pin "3") (pinfunction "3_3") (pintype "passive"))
      (node (ref "U3") (pin "42") (pinfunction "P4.6/RXD2_2_42") (pintype "passive"))
      (node (ref "U5") (pin "6") (pinfunction "6A_6") (pintype "passive"))
    )
    (net (code "65") (name "/RESET") (class "Default")
      (node (ref "C11") (pin "2") (pinfunction "2_2") (pintype "passive"))
      (node (ref "RP7") (pin "5") (pinfunction "5_5") (pintype "passive"))
      (node (ref "SW1") (pin "2") (pinfunction "2_2") (pintype "passive"))
      (node (ref "U2") (pin "7") (pinfunction "NRST_7") (pintype "bidirectional"))
    )
    (net (code "66") (name "/RLED1") (class "Default")
      (node (ref "RP4") (pin "8") (pinfunction "8_8") (pintype "passive"))
      (node (ref "U3") (pin "3") (pinfunction "P0.6/AD6/T3CLKO_3") (pintype "passive"))
    )
    (net (code "67") (name "/RLED2") (class "Default")
      (node (ref "U3") (pin "12") (pinfunction "P1.6/ADC6/RXD_3/XTAL2/MCLKO_2_12") (pintype "passive"))
    )
    (net (code "68") (name "/RLED3") (class "Default")
      (node (ref "RP5") (pin "8") (pinfunction "8_8") (pintype "passive"))
      (node (ref "U3") (pin "6") (pinfunction "P1.1/ADC1/CCP0/TXD2_6") (pintype "passive"))
    )
    (net (code "69") (name "/RLED4") (class "Default")
      (node (ref "U3") (pin "48") (pinfunction "P5.2/RXD4_2_48") (pintype "passive"))
    )
    (net (code "70") (name "/RLED5") (class "Default")
      (node (ref "RP6") (pin "8") (pinfunction "8_8") (pintype "passive"))
      (node (ref "U3") (pin "9") (pinfunction "P1.3/ADC3/MOSI_9") (pintype "passive"))
    )
    (net (code "71") (name "/SCREENRX2 1") (class "Default")
      (node (ref "R46") (pin "2") (pinfunction "2_2") (pintype "passive"))
      (node (ref "U2") (pin "17") (pinfunction "PA3_17") (pintype "bidirectional"))
    )
    (net (code "72") (name "/SCREENRX2 2") (class "Default")
      (node (ref "P8") (pin "3") (pinfunction "3_3") (pintype "passive"))
      (node (ref "R45") (pin "1") (pinfunction "1_1") (pintype "passive"))
    )
    (net (code "73") (name "/SCREENTX2 1") (class "Default")
      (node (ref "R45") (pin "2") (pinfunction "2_2") (pintype "passive"))
      (node (ref "U2") (pin "16") (pinfunction "PA2_16") (pintype "bidirectional"))
    )
    (net (code "74") (name "/SCREENTX2 2") (class "Default")
      (node (ref "P8") (pin "4") (pinfunction "4_4") (pintype "passive"))
      (node (ref "R46") (pin "1") (pinfunction "1_1") (pintype "passive"))
    )
    (net (code "75") (name "/SLAVERXD4 1") (class "Default")
      (node (ref "R26") (pin "2") (pinfunction "2_2") (pintype "passive"))
      (node (ref "R27") (pin "2") (pinfunction "2_2") (pintype "passive"))
      (node (ref "U2") (pin "52") (pinfunction "PC11_52") (pintype "bidirectional"))
    )
    (net (code "76") (name "/SLAVETXD4 1") (class "Default")
      (node (ref "R28") (pin "2") (pinfunction "2_2") (pintype "passive"))
      (node (ref "R31") (pin "2") (pinfunction "2_2") (pintype "passive"))
      (node (ref "U2") (pin "51") (pinfunction "PC10_51") (pintype "bidirectional"))
    )
    (net (code "77") (name "/SP36RXD1 2") (class "Default")
      (node (ref "R31") (pin "1") (pinfunction "1_1") (pintype "passive"))
      (node (ref "U3") (pin "27") (pinfunction "P3.6/~{INT2}/RXD_2/CCP1_2_27") (pintype "passive"))
    )
    (net (code "78") (name "/SP37TXD1 2") (class "Default")
      (node (ref "R26") (pin "1") (pinfunction "1_1") (pintype "passive"))
      (node (ref "U3") (pin "28") (pinfunction "P3.7/~{INT3}/TXD_2/CCP2/CCP2_2_28") (pintype "passive"))
    )
    (net (code "79") (name "/SP50RXD32") (class "Default")
      (node (ref "R28") (pin "1") (pinfunction "1_1") (pintype "passive"))
      (node (ref "U3") (pin "24") (pinfunction "P5.0/RXD3_2_24") (pintype "passive"))
    )
    (net (code "80") (name "/SP51TXD32") (class "Default")
      (node (ref "R27") (pin "1") (pinfunction "1_1") (pintype "passive"))
      (node (ref "U3") (pin "25") (pinfunction "P5.1/TXD3_2_25") (pintype "passive"))
    )
    (net (code "81") (name "/SPARE") (class "Default")
      (node (ref "U3") (pin "46") (pinfunction "P0.3/AD3/TXD4_46") (pintype "passive"))
    )
    (net (code "82") (name "/SWCLK") (class "Default")
      (node (ref "JP1") (pin "3") (pinfunction "3_3") (pintype "passive"))
      (node (ref "U2") (pin "49") (pinfunction "PA14_49") (pintype "bidirectional"))
    )
    (net (code "83") (name "/SWDIO") (class "Default")
      (node (ref "JP1") (pin "2") (pinfunction "2_2") (pintype "passive"))
      (node (ref "U2") (pin "46") (pinfunction "PA13_46") (pintype "bidirectional"))
    )
    (net (code "84") (name "/ULN1_OUT1") (class "Default")
      (node (ref "D5") (pin "K") (pinfunction "K_K") (pintype "passive"))
      (node (ref "REL1") (pin "1") (pintype "passive"))
      (node (ref "U5") (pin "18") (pinfunction "1B_18") (pintype "passive"))
    )
    (net (code "85") (name "/ULN1_OUT2") (class "Default")
      (node (ref "D6") (pin "K") (pinfunction "K_K") (pintype "passive"))
      (node (ref "REL2") (pin "1") (pintype "passive"))
      (node (ref "U5") (pin "17") (pinfunction "2B_17") (pintype "passive"))
    )
    (net (code "86") (name "/ULN1_OUT3") (class "Default")
      (node (ref "D7") (pin "K") (pinfunction "K_K") (pintype "passive"))
      (node (ref "REL3") (pin "1") (pintype "passive"))
      (node (ref "U5") (pin "16") (pinfunction "3B_16") (pintype "passive"))
    )
    (net (code "87") (name "/ULN1_OUT4") (class "Default")
      (node (ref "D8") (pin "K") (pinfunction "K_K") (pintype "passive"))
      (node (ref "REL4") (pin "1") (pintype "passive"))
      (node (ref "U5") (pin "15") (pinfunction "4B_15") (pintype "passive"))
    )
    (net (code "88") (name "/ULN1_OUT5") (class "Default")
      (node (ref "D9") (pin "K") (pinfunction "K_K") (pintype "passive"))
      (node (ref "REL5") (pin "1") (pintype "passive"))
      (node (ref "U5") (pin "14") (pinfunction "5B_14") (pintype "passive"))
    )
    (net (code "89") (name "/ULN1_OUT6") (class "Default")
      (node (ref "D10") (pin "K") (pinfunction "K_K") (pintype "passive"))
      (node (ref "REL6") (pin "1") (pintype "passive"))
      (node (ref "U5") (pin "13") (pinfunction "6B_13") (pintype "passive"))
    )
    (net (code "90") (name "/ULN1_OUT7") (class "Default")
      (node (ref "D11") (pin "K") (pinfunction "K_K") (pintype "passive"))
      (node (ref "REL7") (pin "1") (pintype "passive"))
      (node (ref "U5") (pin "12") (pinfunction "7B_12") (pintype "passive"))
    )
    (net (code "91") (name "/ULN1_OUT8") (class "Default")
      (node (ref "D12") (pin "K") (pinfunction "K_K") (pintype "passive"))
      (node (ref "REL8") (pin "1") (pintype "passive"))
      (node (ref "U5") (pin "11") (pinfunction "8B_11") (pintype "passive"))
    )
    (net (code "92") (name "/UNLOCK") (class "Default")
      (node (ref "R24") (pin "1") (pinfunction "1_1") (pintype "passive"))
      (node (ref "RP2") (pin "3") (pinfunction "3_3") (pintype "passive"))
      (node (ref "U5") (pin "2") (pinfunction "2A_2") (pintype "passive"))
    )
    (net (code "93") (name "/VBAT") (class "Default")
      (node (ref "U2") (pin "1") (pinfunction "VBAT_1") (pintype "power_in"))
    )
    (net (code "94") (name "/WATERVCC") (class "Default")
      (node (ref "J1") (pin "2") (pinfunction "2_2") (pintype "passive"))
      (node (ref "R29") (pin "1") (pinfunction "1_1") (pintype "passive"))
      (node (ref "R3") (pin "2") (pinfunction "2_2") (pintype "passive"))
    )
    (net (code "95") (name "/WATSTATUS1") (class "Default")
      (node (ref "RP3") (pin "8") (pinfunction "8_8") (pintype "passive"))
      (node (ref "U3") (pin "34") (pinfunction "P2.1/A9/SCLK_2_34") (pintype "passive"))
    )
    (net (code "96") (name "/WATSTATUS2") (class "Default")
      (node (ref "U3") (pin "33") (pinfunction "P2.0/A8/RSTOUT_LOW_33") (pintype "passive"))
    )
    (net (code "97") (name "/WATSTATUS3") (class "Default")
      (node (ref "RP3") (pin "7") (pinfunction "7_7") (pintype "passive"))
      (node (ref "U3") (pin "32") (pinfunction "P4.4/~{RD}/CCP4_32") (pintype "passive"))
    )
    (net (code "98") (name "/WATSTATUS4") (class "Default")
      (node (ref "RP3") (pin "6") (pinfunction "6_6") (pintype "passive"))
      (node (ref "U3") (pin "31") (pinfunction "P4.3/SCLK_3_31") (pintype "passive"))
    )
    (net (code "99") (name "/WATSTATUS5") (class "Default")
      (node (ref "RP3") (pin "5") (pinfunction "5_5") (pintype "passive"))
      (node (ref "U3") (pin "30") (pinfunction "P4.2/~{WR}/CCP3_30") (pintype "passive"))
    )
    (net (code "100") (name "GND") (class "Default")
      (node (ref "C1") (pin "1") (pinfunction "1_1") (pintype "passive"))
      (node (ref "C10") (pin "2") (pinfunction "2_2") (pintype "passive"))
      (node (ref "C11") (pin "1") (pinfunction "1_1") (pintype "passive"))
      (node (ref "C14") (pin "2") (pinfunction "2_2") (pintype "passive"))
      (node (ref "C15") (pin "2") (pinfunction "2_2") (pintype "passive"))
      (node (ref "C16") (pin "2") (pinfunction "2_2") (pintype "passive"))
      (node (ref "C17") (pin "2") (pinfunction "2_2") (pintype "passive"))
      (node (ref "C18") (pin "2") (pinfunction "2_2") (pintype "passive"))
      (node (ref "C19") (pin "1") (pinfunction "1_1") (pintype "passive"))
      (node (ref "C2") (pin "1") (pinfunction "1_1") (pintype "passive"))
      (node (ref "C20") (pin "1") (pinfunction "1_1") (pintype "passive"))
      (node (ref "C21") (pin "2") (pinfunction "2_2") (pintype "passive"))
      (node (ref "C22") (pin "1") (pinfunction "1_1") (pintype "passive"))
      (node (ref "C23") (pin "1") (pinfunction "1_1") (pintype "passive"))
      (node (ref "C24") (pin "1") (pinfunction "1_1") (pintype "passive"))
      (node (ref "C25") (pin "1") (pinfunction "1_1") (pintype "passive"))
      (node (ref "C26") (pin "1") (pinfunction "1_1") (pintype "passive"))
      (node (ref "C27") (pin "1") (pinfunction "1_1") (pintype "passive"))
      (node (ref "C28") (pin "1") (pinfunction "1_1") (pintype "passive"))
      (node (ref "C29") (pin "1") (pinfunction "1_1") (pintype "passive"))
      (node (ref "C3") (pin "2") (pinfunction "2_2") (pintype "passive"))
      (node (ref "C30") (pin "1") (pinfunction "1_1") (pintype "passive"))
      (node (ref "C31") (pin "1") (pinfunction "1_1") (pintype "passive"))
      (node (ref "C32") (pin "1") (pinfunction "1_1") (pintype "passive"))
      (node (ref "C33") (pin "1") (pinfunction "1_1") (pintype "passive"))
      (node (ref "C34") (pin "1") (pinfunction "1_1") (pintype "passive"))
      (node (ref "C35") (pin "1") (pinfunction "1_1") (pintype "passive"))
      (node (ref "C36") (pin "1") (pinfunction "1_1") (pintype "passive"))
      (node (ref "C37") (pin "2") (pinfunction "2_2") (pintype "passive"))
      (node (ref "C38") (pin "2") (pinfunction "2_2") (pintype "passive"))
      (node (ref "C4") (pin "2") (pinfunction "2_2") (pintype "passive"))
      (node (ref "C5") (pin "1") (pinfunction "1_1") (pintype "passive"))
      (node (ref "C6") (pin "1") (pinfunction "1_1") (pintype "passive"))
      (node (ref "C7") (pin "2") (pinfunction "2_2") (pintype "passive"))
      (node (ref "C8") (pin "2") (pinfunction "2_2") (pintype "passive"))
      (node (ref "C9") (pin "2") (pinfunction "2_2") (pintype "passive"))
      (node (ref "D1") (pin "K") (pinfunction "K_K") (pintype "passive"))
      (node (ref "D13") (pin "K") (pinfunction "K_K") (pintype "passive"))
      (node (ref "D2") (pin "K") (pinfunction "K_K") (pintype "passive"))
      (node (ref "D20") (pin "K") (pinfunction "K_K") (pintype "passive"))
      (node (ref "D24") (pin "1") (pinfunction "A_1") (pintype "passive"))
      (node (ref "D3") (pin "K") (pinfunction "K_K") (pintype "passive"))
      (node (ref "D4") (pin "K") (pinfunction "K_K") (pintype "passive"))
      (node (ref "J9") (pin "2") (pinfunction "2_2") (pintype "passive"))
      (node (ref "JP1") (pin "1") (pinfunction "1_1") (pintype "passive"))
      (node (ref "JP2") (pin "4") (pinfunction "4_4") (pintype "passive"))
      (node (ref "NTC1") (pin "1") (pinfunction "1_1") (pintype "passive"))
      (node (ref "P1") (pin "1") (pinfunction "1_1") (pintype "passive"))
      (node (ref "P10") (pin "3") (pinfunction "3_3") (pintype "passive"))
      (node (ref "P10") (pin "6") (pinfunction "6_6") (pintype "passive"))
      (node (ref "P11") (pin "3") (pinfunction "3_3") (pintype "passive"))
      (node (ref "P11") (pin "6") (pinfunction "6_6") (pintype "passive"))
      (node (ref "P2") (pin "1") (pinfunction "1_1") (pintype "passive"))
      (node (ref "P3") (pin "1") (pinfunction "1_1") (pintype "passive"))
      (node (ref "P4") (pin "1") (pinfunction "1_1") (pintype "passive"))
      (node (ref "P5") (pin "1") (pinfunction "1_1") (pintype "passive"))
      (node (ref "P6") (pin "1") (pinfunction "1_1") (pintype "passive"))
      (node (ref "P7") (pin "3") (pinfunction "3_3") (pintype "passive"))
      (node (ref "P8") (pin "2") (pinfunction "2_2") (pintype "passive"))
      (node (ref "P9") (pin "3") (pinfunction "3_3") (pintype "passive"))
      (node (ref "P9") (pin "6") (pinfunction "6_6") (pintype "passive"))
      (node (ref "Q1") (pin "2") (pinfunction "E_2") (pintype "passive"))
      (node (ref "R32") (pin "1") (pinfunction "1_1") (pintype "passive"))
      (node (ref "R33") (pin "1") (pinfunction "1_1") (pintype "passive"))
      (node (ref "R48") (pin "2") (pinfunction "2_2") (pintype "passive"))
      (node (ref "R49") (pin "2") (pinfunction "2_2") (pintype "passive"))
      (node (ref "R51") (pin "1") (pinfunction "1_1") (pintype "passive"))
      (node (ref "R52") (pin "1") (pinfunction "1_1") (pintype "passive"))
      (node (ref "R55") (pin "1") (pinfunction "1_1") (pintype "passive"))
      (node (ref "R59") (pin "1") (pinfunction "1_1") (pintype "passive"))
      (node (ref "R61") (pin "2") (pinfunction "2_2") (pintype "passive"))
      (node (ref "RP1") (pin "5") (pinfunction "5_5") (pintype "passive"))
      (node (ref "RP1") (pin "6") (pinfunction "6_6") (pintype "passive"))
      (node (ref "RP1") (pin "7") (pinfunction "7_7") (pintype "passive"))
      (node (ref "RP1") (pin "8") (pinfunction "8_8") (pintype "passive"))
      (node (ref "RP2") (pin "5") (pinfunction "5_5") (pintype "passive"))
      (node (ref "RP2") (pin "6") (pinfunction "6_6") (pintype "passive"))
      (node (ref "RP2") (pin "7") (pinfunction "7_7") (pintype "passive"))
      (node (ref "RP2") (pin "8") (pinfunction "8_8") (pintype "passive"))
      (node (ref "S1") (pin "5") (pinfunction "B4_5") (pintype "passive"))
      (node (ref "S1") (pin "6") (pinfunction "B3_6") (pintype "passive"))
      (node (ref "S1") (pin "7") (pinfunction "B2_7") (pintype "passive"))
      (node (ref "S1") (pin "8") (pinfunction "B1_8") (pintype "passive"))
      (node (ref "SW1") (pin "1") (pinfunction "1_1") (pintype "passive"))
      (node (ref "SW2") (pin "1") (pinfunction "1_1") (pintype "passive"))
      (node (ref "SW3") (pin "1") (pinfunction "1_1") (pintype "passive"))
      (node (ref "SW4") (pin "1") (pinfunction "1_1") (pintype "passive"))
      (node (ref "U1") (pin "12") (pinfunction "GND_12") (pintype "passive"))
      (node (ref "U2") (pin "12") (pinfunction "VSSA_12") (pintype "power_in"))
      (node (ref "U2") (pin "18") (pinfunction "VSS_4_18") (pintype "power_in"))
      (node (ref "U2") (pin "31") (pinfunction "VSS_1_31") (pintype "power_in"))
      (node (ref "U2") (pin "47") (pinfunction "VSS_2_47") (pintype "power_in"))
      (node (ref "U2") (pin "63") (pinfunction "VSS_3_63") (pintype "power_in"))
      (node (ref "U3") (pin "17") (pinfunction "GND_17") (pintype "passive"))
      (node (ref "U4") (pin "10") (pinfunction "GND_10") (pintype "passive"))
      (node (ref "U5") (pin "9") (pinfunction "GND_9") (pintype "passive"))
      (node (ref "U6") (pin "3") (pinfunction "GND_3") (pintype "power_in"))
      (node (ref "U6") (pin "5") (pinfunction "~{ON}/OFF_5") (pintype "input"))
      (node (ref "U7") (pin "2") (pinfunction "VSS_2") (pintype "passive"))
      (node (ref "U8") (pin "1") (pinfunction "A0_1") (pintype "passive"))
      (node (ref "U8") (pin "2") (pinfunction "A1_2") (pintype "passive"))
      (node (ref "U8") (pin "3") (pinfunction "A3_3") (pintype "passive"))
      (node (ref "U8") (pin "4") (pinfunction "GND_4") (pintype "passive"))
      (node (ref "U8") (pin "7") (pinfunction "WP_7") (pintype "passive"))
      (node (ref "VR1") (pin "1") (pinfunction "GND_1") (pintype "passive"))
    )
    (net (code "101") (name "GNDPUM") (class "Default")
      (node (ref "C12") (pin "2") (pinfunction "2_2") (pintype "passive"))
      (node (ref "J1") (pin "1") (pinfunction "1_1") (pintype "passive"))
      (node (ref "J2") (pin "1") (pinfunction "1_1") (pintype "passive"))
      (node (ref "J3") (pin "1") (pinfunction "1_1") (pintype "passive"))
      (node (ref "J4") (pin "1") (pinfunction "1_1") (pintype "passive"))
      (node (ref "J5") (pin "1") (pinfunction "1_1") (pintype "passive"))
      (node (ref "J6") (pin "1") (pinfunction "1_1") (pintype "passive"))
      (node (ref "J7") (pin "1") (pinfunction "1_1") (pintype "passive"))
      (node (ref "J8") (pin "1") (pinfunction "1_1") (pintype "passive"))
      (node (ref "L1") (pin "4") (pinfunction "B_4") (pintype "passive"))
    )
    (net (code "102") (name "Net-(C13-Pad2)") (class "Default")
      (node (ref "C13") (pin "2") (pinfunction "2_2") (pintype "passive"))
      (node (ref "L1") (pin "3") (pinfunction "B_3") (pintype "passive"))
    )
    (net (code "103") (name "Net-(D1-PadA)") (class "Default")
      (node (ref "D1") (pin "A") (pinfunction "A_A") (pintype "passive"))
      (node (ref "R1") (pin "1") (pinfunction "1_1") (pintype "passive"))
    )
    (net (code "104") (name "Net-(D2-PadA)") (class "Default")
      (node (ref "D2") (pin "A") (pinfunction "A_A") (pintype "passive"))
      (node (ref "R2") (pin "1") (pinfunction "1_1") (pintype "passive"))
    )
    (net (code "105") (name "Net-(D3-PadA)") (class "Default")
      (node (ref "D3") (pin "A") (pinfunction "A_A") (pintype "passive"))
      (node (ref "R6") (pin "1") (pinfunction "1_1") (pintype "passive"))
    )
    (net (code "106") (name "Net-(D4-PadA)") (class "Default")
      (node (ref "D4") (pin "A") (pinfunction "A_A") (pintype "passive"))
      (node (ref "R7") (pin "1") (pinfunction "1_1") (pintype "passive"))
    )
    (net (code "107") (name "Net-(D5-PadA)") (class "Default")
      (node (ref "D5") (pin "A") (pinfunction "A_A") (pintype "passive"))
      (node (ref "R8") (pin "1") (pinfunction "1_1") (pintype "passive"))
    )
    (net (code "108") (name "Net-(D6-PadA)") (class "Default")
      (node (ref "D6") (pin "A") (pinfunction "A_A") (pintype "passive"))
      (node (ref "R9") (pin "1") (pinfunction "1_1") (pintype "passive"))
    )
    (net (code "109") (name "Net-(D7-PadA)") (class "Default")
      (node (ref "D7") (pin "A") (pinfunction "A_A") (pintype "passive"))
      (node (ref "R10") (pin "1") (pinfunction "1_1") (pintype "passive"))
    )
    (net (code "110") (name "Net-(D8-PadA)") (class "Default")
      (node (ref "D8") (pin "A") (pinfunction "A_A") (pintype "passive"))
      (node (ref "R16") (pin "1") (pinfunction "1_1") (pintype "passive"))
    )
    (net (code "111") (name "Net-(D9-PadA)") (class "Default")
      (node (ref "D9") (pin "A") (pinfunction "A_A") (pintype "passive"))
      (node (ref "R17") (pin "1") (pinfunction "1_1") (pintype "passive"))
    )
    (net (code "112") (name "Net-(D10-PadA)") (class "Default")
      (node (ref "D10") (pin "A") (pinfunction "A_A") (pintype "passive"))
      (node (ref "R18") (pin "1") (pinfunction "1_1") (pintype "passive"))
    )
    (net (code "113") (name "Net-(D11-PadA)") (class "Default")
      (node (ref "D11") (pin "A") (pinfunction "A_A") (pintype "passive"))
      (node (ref "R21") (pin "1") (pinfunction "1_1") (pintype "passive"))
    )
    (net (code "114") (name "Net-(D12-PadA)") (class "Default")
      (node (ref "D12") (pin "A") (pinfunction "A_A") (pintype "passive"))
      (node (ref "R22") (pin "1") (pinfunction "1_1") (pintype "passive"))
    )
    (net (code "115") (name "Net-(D13-PadA)") (class "Default")
      (node (ref "D13") (pin "A") (pinfunction "A_A") (pintype "passive"))
      (node (ref "R30") (pin "1") (pinfunction "1_1") (pintype "passive"))
    )
    (net (code "116") (name "Net-(D14-PadA)") (class "Default")
      (node (ref "D14") (pin "A") (pinfunction "A_A") (pintype "passive"))
      (node (ref "RP9") (pin "8") (pinfunction "8_8") (pintype "passive"))
    )
    (net (code "117") (name "Net-(D15-K)") (class "Default")
      (node (ref "D15") (pin "2") (pinfunction "K_2") (pintype "passive"))
      (node (ref "R43") (pin "1") (pinfunction "1_1") (pintype "passive"))
    )
    (net (code "118") (name "Net-(D16-PadA)") (class "Default")
      (node (ref "D16") (pin "A") (pinfunction "A_A") (pintype "passive"))
      (node (ref "RP9") (pin "7") (pinfunction "7_7") (pintype "passive"))
    )
    (net (code "119") (name "Net-(D17-PadK)") (class "Default")
      (node (ref "D17") (pin "K") (pinfunction "K_K") (pintype "passive"))
      (node (ref "R48") (pin "1") (pinfunction "1_1") (pintype "passive"))
    )
    (net (code "120") (name "Net-(D18-PadK)") (class "Default")
      (node (ref "D18") (pin "K") (pinfunction "K_K") (pintype "passive"))
      (node (ref "R49") (pin "1") (pinfunction "1_1") (pintype "passive"))
    )
    (net (code "121") (name "Net-(D19-PadK)") (class "Default")
      (node (ref "D19") (pin "K") (pinfunction "K_K") (pintype "passive"))
      (node (ref "R61") (pin "1") (pinfunction "1_1") (pintype "passive"))
    )
    (net (code "122") (name "Net-(D20-PadA)") (class "Default")
      (node (ref "D20") (pin "A") (pinfunction "A_A") (pintype "passive"))
      (node (ref "R44") (pin "1") (pinfunction "1_1") (pintype "passive"))
    )
    (net (code "123") (name "Net-(D21-PadA)") (class "Default")
      (node (ref "D21") (pin "A") (pinfunction "A_A") (pintype "passive"))
      (node (ref "RP9") (pin "5") (pinfunction "5_5") (pintype "passive"))
    )
    (net (code "124") (name "Net-(D22-K)") (class "Default")
      (node (ref "C13") (pin "1") (pinfunction "1_1") (pintype "passive"))
      (node (ref "D22") (pin "2") (pinfunction "K_2") (pintype "passive"))
      (node (ref "F1") (pin "1") (pinfunction "1_1") (pintype "passive"))
    )
    (net (code "125") (name "Net-(D23-K)") (class "Default")
      (node (ref "C14") (pin "1") (pinfunction "1_1") (pintype "passive"))
      (node (ref "C16") (pin "1") (pinfunction "1_1") (pintype "passive"))
      (node (ref "D23") (pin "2") (pinfunction "K_2") (pintype "passive"))
      (node (ref "U7") (pin "1") (pinfunction "Vin_1") (pintype "passive"))
    )
    (net (code "126") (name "Net-(D24-K)") (class "Default")
      (node (ref "D24") (pin "2") (pinfunction "K_2") (pintype "passive"))
      (node (ref "L2") (pin "1") (pinfunction "1_1") (pintype "passive"))
      (node (ref "U6") (pin "2") (pinfunction "OUT_2") (pintype "power_in"))
    )
    (net (code "127") (name "Net-(D25-K)") (class "Default")
      (node (ref "C22") (pin "2") (pinfunction "2_2") (pintype "passive"))
      (node (ref "C37") (pin "1") (pinfunction "1_1") (pintype "passive"))
      (node (ref "D25") (pin "2") (pinfunction "K_2") (pintype "passive"))
      (node (ref "VR1") (pin "3") (pinfunction "Vin_3") (pintype "passive"))
    )
    (net (code "128") (name "Net-(D26-PadA)") (class "Default")
      (node (ref "D26") (pin "A") (pinfunction "A_A") (pintype "passive"))
      (node (ref "RP9") (pin "6") (pinfunction "6_6") (pintype "passive"))
    )
    (net (code "129") (name "Net-(F1-Pad2)") (class "Default")
      (node (ref "F1") (pin "2") (pinfunction "2_2") (pintype "passive"))
      (node (ref "L1") (pin "1") (pinfunction "A_1") (pintype "passive"))
    )
    (net (code "130") (name "Net-(FUSE1-Pad1)") (class "Default")
      (node (ref "FUSE1") (pin "1") (pinfunction "1_1") (pintype "passive"))
      (node (ref "J9") (pin "1") (pinfunction "1_1") (pintype "passive"))
    )
    (net (code "131") (name "Net-(J2-Pad2)") (class "Default")
      (node (ref "J2") (pin "2") (pinfunction "2_2") (pintype "passive"))
      (node (ref "R4") (pin "2") (pinfunction "2_2") (pintype "passive"))
    )
    (net (code "132") (name "Net-(J3-Pad2)") (class "Default")
      (node (ref "J3") (pin "2") (pinfunction "2_2") (pintype "passive"))
      (node (ref "R5") (pin "2") (pinfunction "2_2") (pintype "passive"))
    )
    (net (code "133") (name "Net-(J4-Pad2)") (class "Default")
      (node (ref "J4") (pin "2") (pinfunction "2_2") (pintype "passive"))
      (node (ref "R11") (pin "2") (pinfunction "2_2") (pintype "passive"))
    )
    (net (code "134") (name "Net-(J5-Pad2)") (class "Default")
      (node (ref "J5") (pin "2") (pinfunction "2_2") (pintype "passive"))
      (node (ref "R12") (pin "2") (pinfunction "2_2") (pintype "passive"))
    )
    (net (code "135") (name "Net-(J6-Pad2)") (class "Default")
      (node (ref "J6") (pin "2") (pinfunction "2_2") (pintype "passive"))
      (node (ref "R13") (pin "2") (pinfunction "2_2") (pintype "passive"))
    )
    (net (code "136") (name "Net-(J7-Pad2)") (class "Default")
      (node (ref "J7") (pin "2") (pinfunction "2_2") (pintype "passive"))
      (node (ref "R19") (pin "2") (pinfunction "2_2") (pintype "passive"))
    )
    (net (code "137") (name "Net-(J8-Pad2)") (class "Default")
      (node (ref "J8") (pin "2") (pinfunction "2_2") (pintype "passive"))
      (node (ref "R20") (pin "2") (pinfunction "2_2") (pintype "passive"))
    )
    (net (code "138") (name "Net-(LS1-B)") (class "Default")
      (node (ref "LS1") (pin "2") (pinfunction "B_2") (pintype "passive"))
      (node (ref "Q1") (pin "3") (pinfunction "C_3") (pintype "passive"))
    )
    (net (code "139") (name "Net-(P1-Pad2)") (class "Default")
      (node (ref "P1") (pin "2") (pinfunction "2_2") (pintype "passive"))
      (node (ref "RP3") (pin "1") (pinfunction "1_1") (pintype "passive"))
    )
    (net (code "140") (name "Net-(P1-Pad3)") (class "Default")
      (node (ref "P1") (pin "3") (pinfunction "3_3") (pintype "passive"))
      (node (ref "P2") (pin "3") (pinfunction "3_3") (pintype "passive"))
      (node (ref "P3") (pin "3") (pinfunction "3_3") (pintype "passive"))
      (node (ref "R29") (pin "2") (pinfunction "2_2") (pintype "passive"))
    )
    (net (code "141") (name "Net-(P2-Pad2)") (class "Default")
      (node (ref "P2") (pin "2") (pinfunction "2_2") (pintype "passive"))
      (node (ref "RP3") (pin "2") (pinfunction "2_2") (pintype "passive"))
    )
    (net (code "142") (name "Net-(P3-Pad2)") (class "Default")
      (node (ref "P3") (pin "2") (pinfunction "2_2") (pintype "passive"))
      (node (ref "RP3") (pin "4") (pinfunction "4_4") (pintype "passive"))
    )
    (net (code "143") (name "Net-(P4-Pad2)") (class "Default")
      (node (ref "P4") (pin "2") (pinfunction "2_2") (pintype "passive"))
      (node (ref "RP4") (pin "3") (pinfunction "3_3") (pintype "passive"))
    )
    (net (code "144") (name "Net-(P4-Pad3)") (class "Default")
      (node (ref "P4") (pin "3") (pinfunction "3_3") (pintype "passive"))
      (node (ref "RP4") (pin "2") (pinfunction "2_2") (pintype "passive"))
    )
    (net (code "145") (name "Net-(P4-Pad4)") (class "Default")
      (node (ref "P4") (pin "4") (pinfunction "4_4") (pintype "passive"))
      (node (ref "RP4") (pin "1") (pinfunction "1_1") (pintype "passive"))
    )
    (net (code "146") (name "Net-(P4-Pad5)") (class "Default")
      (node (ref "P4") (pin "5") (pinfunction "5_5") (pintype "passive"))
      (node (ref "R35") (pin "2") (pinfunction "2_2") (pintype "passive"))
    )
    (net (code "147") (name "Net-(P5-Pad2)") (class "Default")
      (node (ref "P5") (pin "2") (pinfunction "2_2") (pintype "passive"))
      (node (ref "RP5") (pin "3") (pinfunction "3_3") (pintype "passive"))
    )
    (net (code "148") (name "Net-(P5-Pad3)") (class "Default")
      (node (ref "P5") (pin "3") (pinfunction "3_3") (pintype "passive"))
      (node (ref "RP5") (pin "2") (pinfunction "2_2") (pintype "passive"))
    )
    (net (code "149") (name "Net-(P5-Pad4)") (class "Default")
      (node (ref "P5") (pin "4") (pinfunction "4_4") (pintype "passive"))
      (node (ref "RP5") (pin "1") (pinfunction "1_1") (pintype "passive"))
    )
    (net (code "150") (name "Net-(P5-Pad5)") (class "Default")
      (node (ref "P5") (pin "5") (pinfunction "5_5") (pintype "passive"))
      (node (ref "R36") (pin "2") (pinfunction "2_2") (pintype "passive"))
    )
    (net (code "151") (name "Net-(P6-Pad2)") (class "Default")
      (node (ref "P6") (pin "2") (pinfunction "2_2") (pintype "passive"))
      (node (ref "RP6") (pin "3") (pinfunction "3_3") (pintype "passive"))
    )
    (net (code "152") (name "Net-(P6-Pad3)") (class "Default")
      (node (ref "P6") (pin "3") (pinfunction "3_3") (pintype "passive"))
      (node (ref "RP6") (pin "2") (pinfunction "2_2") (pintype "passive"))
    )
    (net (code "153") (name "Net-(P6-Pad4)") (class "Default")
      (node (ref "P6") (pin "4") (pinfunction "4_4") (pintype "passive"))
      (node (ref "RP6") (pin "1") (pinfunction "1_1") (pintype "passive"))
    )
    (net (code "154") (name "Net-(P6-Pad5)") (class "Default")
      (node (ref "P6") (pin "5") (pinfunction "5_5") (pintype "passive"))
      (node (ref "R37") (pin "2") (pinfunction "2_2") (pintype "passive"))
    )
    (net (code "155") (name "Net-(P7-Pad12)") (class "Default")
      (node (ref "P7") (pin "12") (pinfunction "12_12") (pintype "passive"))
      (node (ref "R47") (pin "1") (pinfunction "1_1") (pintype "passive"))
    )
    (net (code "156") (name "Net-(P9-Pad5)") (class "Default")
      (node (ref "P9") (pin "5") (pinfunction "5_5") (pintype "passive"))
      (node (ref "R60") (pin "2") (pinfunction "2_2") (pintype "passive"))
    )
    (net (code "157") (name "Net-(P10-Pad5)") (class "Default")
      (node (ref "P10") (pin "5") (pinfunction "5_5") (pintype "passive"))
      (node (ref "R54") (pin "2") (pinfunction "2_2") (pintype "passive"))
    )
    (net (code "158") (name "Net-(P11-Pad5)") (class "Default")
      (node (ref "P11") (pin "5") (pinfunction "5_5") (pintype "passive"))
      (node (ref "R58") (pin "2") (pinfunction "2_2") (pintype "passive"))
    )
    (net (code "159") (name "Net-(Q1-B)") (class "Default")
      (node (ref "Q1") (pin "1") (pinfunction "B_1") (pintype "passive"))
      (node (ref "R50") (pin "1") (pinfunction "1_1") (pintype "passive"))
      (node (ref "R51") (pin "2") (pinfunction "2_2") (pintype "passive"))
    )
    (net (code "160") (name "Net-(R3-Pad1)") (class "Default")
      (node (ref "R3") (pin "1") (pinfunction "1_1") (pintype "passive"))
      (node (ref "REL1") (pin "3") (pintype "passive"))
    )
    (net (code "161") (name "Net-(R4-Pad1)") (class "Default")
      (node (ref "R4") (pin "1") (pinfunction "1_1") (pintype "passive"))
      (node (ref "REL2") (pin "3") (pintype "passive"))
    )
    (net (code "162") (name "Net-(R5-Pad1)") (class "Default")
      (node (ref "R5") (pin "1") (pinfunction "1_1") (pintype "passive"))
      (node (ref "REL3") (pin "3") (pintype "passive"))
    )
    (net (code "163") (name "Net-(R11-Pad1)") (class "Default")
      (node (ref "R11") (pin "1") (pinfunction "1_1") (pintype "passive"))
      (node (ref "REL4") (pin "3") (pintype "passive"))
    )
    (net (code "164") (name "Net-(R12-Pad1)") (class "Default")
      (node (ref "R12") (pin "1") (pinfunction "1_1") (pintype "passive"))
      (node (ref "REL5") (pin "3") (pintype "passive"))
    )
    (net (code "165") (name "Net-(R13-Pad1)") (class "Default")
      (node (ref "R13") (pin "1") (pinfunction "1_1") (pintype "passive"))
      (node (ref "REL6") (pin "3") (pintype "passive"))
    )
    (net (code "166") (name "Net-(R19-Pad1)") (class "Default")
      (node (ref "R19") (pin "1") (pinfunction "1_1") (pintype "passive"))
      (node (ref "REL7") (pin "3") (pintype "passive"))
    )
    (net (code "167") (name "Net-(R20-Pad1)") (class "Default")
      (node (ref "R20") (pin "1") (pinfunction "1_1") (pintype "passive"))
      (node (ref "REL8") (pin "3") (pintype "passive"))
    )
    (net (code "168") (name "Net-(U1-LINKA)") (class "Default")
      (node (ref "R1") (pin "2") (pinfunction "2_2") (pintype "passive"))
      (node (ref "U1") (pin "1") (pinfunction "LINKA_1") (pintype "passive"))
    )
    (net (code "169") (name "Net-(U1-LINKB)") (class "Default")
      (node (ref "R2") (pin "2") (pinfunction "2_2") (pintype "passive"))
      (node (ref "U1") (pin "2") (pinfunction "LINKB_2") (pintype "passive"))
    )
    (net (code "170") (name "Net-(U1-NET)") (class "Default")
      (node (ref "R7") (pin "2") (pinfunction "2_2") (pintype "passive"))
      (node (ref "U1") (pin "15") (pinfunction "NET_15") (pintype "passive"))
    )
    (net (code "171") (name "Net-(U1-WORK)") (class "Default")
      (node (ref "R6") (pin "2") (pinfunction "2_2") (pintype "passive"))
      (node (ref "U1") (pin "9") (pinfunction "WORK_9") (pintype "passive"))
    )
    (net (code "172") (name "Net-(U2A-PA15)") (class "Default")
      (node (ref "R24") (pin "2") (pinfunction "2_2") (pintype "passive"))
      (node (ref "U2") (pin "50") (pinfunction "PA15_50") (pintype "bidirectional"))
    )
    (net (code "173") (name "Net-(U4-LED_LINK)") (class "Default")
      (node (ref "R30") (pin "2") (pinfunction "2_2") (pintype "passive"))
      (node (ref "U4") (pin "12") (pinfunction "LED_LINK_12") (pintype "passive"))
    )
    (net (code "174") (name "Net-(U6-VIN)") (class "Default")
      (node (ref "C18") (pin "1") (pinfunction "1_1") (pintype "passive"))
      (node (ref "C19") (pin "2") (pinfunction "2_2") (pintype "passive"))
      (node (ref "R53") (pin "1") (pinfunction "1_1") (pintype "passive"))
      (node (ref "U6") (pin "1") (pinfunction "VIN_1") (pintype "power_in"))
    )
    (net (code "175") (name "VCC3V3") (class "Default")
      (node (ref "C23") (pin "2") (pinfunction "2_2") (pintype "passive"))
      (node (ref "C24") (pin "2") (pinfunction "2_2") (pintype "passive"))
      (node (ref "C25") (pin "2") (pinfunction "2_2") (pintype "passive"))
      (node (ref "C26") (pin "2") (pinfunction "2_2") (pintype "passive"))
      (node (ref "C27") (pin "2") (pinfunction "2_2") (pintype "passive"))
      (node (ref "C28") (pin "2") (pinfunction "2_2") (pintype "passive"))
      (node (ref "C29") (pin "2") (pinfunction "2_2") (pintype "passive"))
      (node (ref "C30") (pin "2") (pinfunction "2_2") (pintype "passive"))
      (node (ref "C31") (pin "2") (pinfunction "2_2") (pintype "passive"))
      (node (ref "C32") (pin "2") (pinfunction "2_2") (pintype "passive"))
      (node (ref "C33") (pin "2") (pinfunction "2_2") (pintype "passive"))
      (node (ref "C34") (pin "2") (pinfunction "2_2") (pintype "passive"))
      (node (ref "C35") (pin "2") (pinfunction "2_2") (pintype "passive"))
      (node (ref "C36") (pin "2") (pinfunction "2_2") (pintype "passive"))
      (node (ref "C38") (pin "1") (pinfunction "1_1") (pintype "passive"))
      (node (ref "JP1") (pin "4") (pinfunction "4_4") (pintype "passive"))
      (node (ref "R44") (pin "2") (pinfunction "2_2") (pintype "passive"))
      (node (ref "R56") (pin "2") (pinfunction "2_2") (pintype "passive"))
      (node (ref "R57") (pin "2") (pinfunction "2_2") (pintype "passive"))
      (node (ref "RP7") (pin "1") (pinfunction "1_1") (pintype "passive"))
      (node (ref "RP7") (pin "2") (pinfunction "2_2") (pintype "passive"))
      (node (ref "RP7") (pin "3") (pinfunction "3_3") (pintype "passive"))
      (node (ref "RP7") (pin "4") (pinfunction "4_4") (pintype "passive"))
      (node (ref "RP8") (pin "1") (pinfunction "1_1") (pintype "passive"))
      (node (ref "RP8") (pin "2") (pinfunction "2_2") (pintype "passive"))
      (node (ref "RP8") (pin "3") (pinfunction "3_3") (pintype "passive"))
      (node (ref "RP8") (pin "4") (pinfunction "4_4") (pintype "passive"))
      (node (ref "RP9") (pin "1") (pinfunction "1_1") (pintype "passive"))
      (node (ref "RP9") (pin "2") (pinfunction "2_2") (pintype "passive"))
      (node (ref "RP9") (pin "3") (pinfunction "3_3") (pintype "passive"))
      (node (ref "RP9") (pin "4") (pinfunction "4_4") (pintype "passive"))
      (node (ref "U2") (pin "13") (pinfunction "VDDA_13") (pintype "power_in"))
      (node (ref "U2") (pin "19") (pinfunction "VDD_4_19") (pintype "power_in"))
      (node (ref "U2") (pin "32") (pinfunction "VDD_1_32") (pintype "power_in"))
      (node (ref "U2") (pin "48") (pinfunction "VDD_2_48") (pintype "power_in"))
      (node (ref "U2") (pin "64") (pinfunction "VDD_3_64") (pintype "power_in"))
      (node (ref "U4") (pin "11") (pinfunction "VDD_11") (pintype "passive"))
      (node (ref "U8") (pin "8") (pinfunction "VCC_8") (pintype "passive"))
      (node (ref "VR1") (pin "2") (pinfunction "Vout_2") (pintype "passive"))
    )
    (net (code "176") (name "VCC5V") (class "Default")
      (node (ref "C20") (pin "2") (pinfunction "2_2") (pintype "passive"))
      (node (ref "C21") (pin "1") (pinfunction "1_1") (pintype "passive"))
      (node (ref "D17") (pin "A") (pinfunction "A_A") (pintype "passive"))
      (node (ref "D25") (pin "1") (pinfunction "A_1") (pintype "passive"))
      (node (ref "L2") (pin "2") (pinfunction "2_2") (pintype "passive"))
      (node (ref "LS1") (pin "1") (pinfunction "A_1") (pintype "passive"))
      (node (ref "P10") (pin "2") (pinfunction "2_2") (pintype "passive"))
      (node (ref "P10") (pin "4") (pinfunction "4_4") (pintype "passive"))
      (node (ref "P11") (pin "2") (pinfunction "2_2") (pintype "passive"))
      (node (ref "P11") (pin "4") (pinfunction "4_4") (pintype "passive"))
      (node (ref "P7") (pin "2") (pinfunction "2_2") (pintype "passive"))
      (node (ref "P8") (pin "1") (pinfunction "1_1") (pintype "passive"))
      (node (ref "P9") (pin "2") (pinfunction "2_2") (pintype "passive"))
      (node (ref "P9") (pin "4") (pinfunction "4_4") (pintype "passive"))
      (node (ref "R35") (pin "1") (pinfunction "1_1") (pintype "passive"))
      (node (ref "R36") (pin "1") (pinfunction "1_1") (pintype "passive"))
      (node (ref "R37") (pin "1") (pinfunction "1_1") (pintype "passive"))
      (node (ref "R38") (pin "1") (pinfunction "1_1") (pintype "passive"))
      (node (ref "R39") (pin "1") (pinfunction "1_1") (pintype "passive"))
      (node (ref "R40") (pin "1") (pinfunction "1_1") (pintype "passive"))
      (node (ref "U6") (pin "4") (pinfunction "FB_4") (pintype "input"))
    )
    (net (code "177") (name "VCC12V") (class "Default")
      (node (ref "C10") (pin "1") (pinfunction "1_1") (pintype "passive"))
      (node (ref "C8") (pin "1") (pinfunction "1_1") (pintype "passive"))
      (node (ref "D15") (pin "1") (pinfunction "A_1") (pintype "passive"))
      (node (ref "D22") (pin "1") (pinfunction "A_1") (pintype "passive"))
      (node (ref "D23") (pin "1") (pinfunction "A_1") (pintype "passive"))
      (node (ref "FUSE1") (pin "2") (pinfunction "2_2") (pintype "passive"))
      (node (ref "NTC1") (pin "2") (pinfunction "2_2") (pintype "passive"))
      (node (ref "R53") (pin "2") (pinfunction "2_2") (pintype "passive"))
      (node (ref "U1") (pin "13") (pinfunction "DC5-16V_13") (pintype "passive"))
    )
    (net (code "178") (name "VCC12VPUM") (class "Default")
      (node (ref "C12") (pin "1") (pinfunction "1_1") (pintype "passive"))
      (node (ref "D18") (pin "A") (pinfunction "A_A") (pintype "passive"))
      (node (ref "L1") (pin "2") (pinfunction "A_2") (pintype "passive"))
      (node (ref "REL2") (pin "2") (pintype "passive"))
      (node (ref "REL3") (pin "2") (pintype "passive"))
      (node (ref "REL4") (pin "2") (pintype "passive"))
      (node (ref "REL5") (pin "2") (pintype "passive"))
      (node (ref "REL6") (pin "2") (pintype "passive"))
      (node (ref "REL7") (pin "2") (pintype "passive"))
      (node (ref "REL8") (pin "2") (pintype "passive"))
    )
    (net (code "179") (name "VCC12VREL") (class "Default")
      (node (ref "C3") (pin "1") (pinfunction "1_1") (pintype "passive"))
      (node (ref "C4") (pin "1") (pinfunction "1_1") (pintype "passive"))
      (node (ref "C7") (pin "1") (pinfunction "1_1") (pintype "passive"))
      (node (ref "C9") (pin "1") (pinfunction "1_1") (pintype "passive"))
      (node (ref "R10") (pin "2") (pinfunction "2_2") (pintype "passive"))
      (node (ref "R16") (pin "2") (pinfunction "2_2") (pintype "passive"))
      (node (ref "R17") (pin "2") (pinfunction "2_2") (pintype "passive"))
      (node (ref "R18") (pin "2") (pinfunction "2_2") (pintype "passive"))
      (node (ref "R21") (pin "2") (pinfunction "2_2") (pintype "passive"))
      (node (ref "R22") (pin "2") (pinfunction "2_2") (pintype "passive"))
      (node (ref "R43") (pin "2") (pinfunction "2_2") (pintype "passive"))
      (node (ref "R8") (pin "2") (pinfunction "2_2") (pintype "passive"))
      (node (ref "R9") (pin "2") (pinfunction "2_2") (pintype "passive"))
      (node (ref "REL1") (pin "5") (pintype "passive"))
      (node (ref "REL2") (pin "5") (pintype "passive"))
      (node (ref "REL3") (pin "5") (pintype "passive"))
      (node (ref "REL4") (pin "5") (pintype "passive"))
      (node (ref "REL5") (pin "5") (pintype "passive"))
      (node (ref "REL6") (pin "5") (pintype "passive"))
      (node (ref "REL7") (pin "5") (pintype "passive"))
      (node (ref "REL8") (pin "5") (pintype "passive"))
      (node (ref "U5") (pin "10") (pinfunction "COM_10") (pintype "passive"))
    )
    (net (code "180") (name "VCCP5V") (class "Default")
      (node (ref "C15") (pin "1") (pinfunction "1_1") (pintype "passive"))
      (node (ref "C17") (pin "1") (pinfunction "1_1") (pintype "passive"))
      (node (ref "D19") (pin "A") (pinfunction "A_A") (pintype "passive"))
      (node (ref "JP2") (pin "1") (pinfunction "1_1") (pintype "passive"))
      (node (ref "REL1") (pin "2") (pintype "passive"))
      (node (ref "U3") (pin "15") (pinfunction "VCC_15") (pintype "passive"))
      (node (ref "U7") (pin "3") (pinfunction "Vout_3") (pintype "passive"))
    )
    (net (code "181") (name "unconnected-(P9-Pad1)") (class "Default")
      (node (ref "P9") (pin "1") (pinfunction "1_1") (pintype "passive"))
    )
    (net (code "182") (name "unconnected-(P10-Pad1)") (class "Default")
      (node (ref "P10") (pin "1") (pinfunction "1_1") (pintype "passive"))
    )
    (net (code "183") (name "unconnected-(P11-Pad1)") (class "Default")
      (node (ref "P11") (pin "1") (pinfunction "1_1") (pintype "passive"))
    )
    (net (code "184") (name "unconnected-(RP3-Pad3)") (class "Default")
      (node (ref "RP3") (pin "3") (pinfunction "3_3") (pintype "passive"))
    )
    (net (code "185") (name "unconnected-(RP4-Pad4)") (class "Default")
      (node (ref "RP4") (pin "4") (pinfunction "4_4") (pintype "passive"))
    )
    (net (code "186") (name "unconnected-(RP4-Pad5)") (class "Default")
      (node (ref "RP4") (pin "5") (pinfunction "5_5") (pintype "passive"))
    )
    (net (code "187") (name "unconnected-(RP5-Pad4)") (class "Default")
      (node (ref "RP5") (pin "4") (pinfunction "4_4") (pintype "passive"))
    )
    (net (code "188") (name "unconnected-(RP5-Pad5)") (class "Default")
      (node (ref "RP5") (pin "5") (pinfunction "5_5") (pintype "passive"))
    )
    (net (code "189") (name "unconnected-(RP6-Pad4)") (class "Default")
      (node (ref "RP6") (pin "4") (pinfunction "4_4") (pintype "passive"))
    )
    (net (code "190") (name "unconnected-(RP6-Pad5)") (class "Default")
      (node (ref "RP6") (pin "5") (pinfunction "5_5") (pintype "passive"))
    )
    (net (code "191") (name "unconnected-(U1-DC5-16V-Pad14)") (class "Default")
      (node (ref "U1") (pin "14") (pinfunction "DC5-16V_14") (pintype "passive"))
    )
    (net (code "192") (name "unconnected-(U1-GND-Pad11)") (class "Default")
      (node (ref "U1") (pin "11") (pinfunction "GND_11") (pintype "passive"))
    )
    (net (code "193") (name "unconnected-(U1-MIC_N-Pad21)") (class "Default")
      (node (ref "U1") (pin "21") (pinfunction "MIC_N_21") (pintype "passive"))
    )
    (net (code "194") (name "unconnected-(U1-MIC_P-Pad20)") (class "Default")
      (node (ref "U1") (pin "20") (pinfunction "MIC_P_20") (pintype "passive"))
    )
    (net (code "195") (name "unconnected-(U1-NC-Pad3)") (class "Default")
      (node (ref "U1") (pin "3") (pinfunction "NC_3") (pintype "passive"))
    )
    (net (code "196") (name "unconnected-(U1-NC-Pad4)") (class "Default")
      (node (ref "U1") (pin "4") (pinfunction "NC_4") (pintype "passive"))
    )
    (net (code "197") (name "unconnected-(U1-PWRKEY-Pad10)") (class "Default")
      (node (ref "U1") (pin "10") (pinfunction "PWRKEY_10") (pintype "passive"))
    )
    (net (code "198") (name "unconnected-(U1-RCV_N-Pad23)") (class "Default")
      (node (ref "U1") (pin "23") (pinfunction "RCV_N_23") (pintype "passive"))
    )
    (net (code "199") (name "unconnected-(U1-RCV_P-Pad22)") (class "Default")
      (node (ref "U1") (pin "22") (pinfunction "RCV_P_22") (pintype "passive"))
    )
    (net (code "200") (name "unconnected-(U1-RELOAD-Pad18)") (class "Default")
      (node (ref "U1") (pin "18") (pinfunction "RELOAD_18") (pintype "passive"))
    )
    (net (code "201") (name "unconnected-(U1-RESET-Pad19)") (class "Default")
      (node (ref "U1") (pin "19") (pinfunction "RESET_19") (pintype "passive"))
    )
    (net (code "202") (name "unconnected-(U1-RS485_EN-Pad17)") (class "Default")
      (node (ref "U1") (pin "17") (pinfunction "RS485_EN_17") (pintype "passive"))
    )
    (net (code "203") (name "unconnected-(U1-URXD2-Pad8)") (class "Default")
      (node (ref "U1") (pin "8") (pinfunction "URXD2_8") (pintype "passive"))
    )
    (net (code "204") (name "unconnected-(U1-UTXD2-Pad5)") (class "Default")
      (node (ref "U1") (pin "5") (pinfunction "UTXD2_5") (pintype "passive"))
    )
    (net (code "205") (name "unconnected-(U1-VCAP-Pad16)") (class "Default")
      (node (ref "U1") (pin "16") (pinfunction "VCAP_16") (pintype "passive"))
    )
    (net (code "206") (name "unconnected-(U2A-PA0-WKUP-Pad14)") (class "Default")
      (node (ref "U2") (pin "14") (pinfunction "PA0-WKUP_14") (pintype "bidirectional"))
    )
    (net (code "207") (name "unconnected-(U2A-PA1-Pad15)") (class "Default")
      (node (ref "U2") (pin "15") (pinfunction "PA1_15") (pintype "bidirectional"))
    )
    (net (code "208") (name "unconnected-(U2A-PA8-Pad41)") (class "Default")
      (node (ref "U2") (pin "41") (pinfunction "PA8_41") (pintype "bidirectional"))
    )
    (net (code "209") (name "unconnected-(U2A-PA11-Pad44)") (class "Default")
      (node (ref "U2") (pin "44") (pinfunction "PA11_44") (pintype "bidirectional"))
    )
    (net (code "210") (name "unconnected-(U2A-PA12-Pad45)") (class "Default")
      (node (ref "U2") (pin "45") (pinfunction "PA12_45") (pintype "bidirectional"))
    )
    (net (code "211") (name "unconnected-(U2A-PB3-Pad55)") (class "Default")
      (node (ref "U2") (pin "55") (pinfunction "PB3_55") (pintype "bidirectional"))
    )
    (net (code "212") (name "unconnected-(U2A-PB4-Pad56)") (class "Default")
      (node (ref "U2") (pin "56") (pinfunction "PB4_56") (pintype "bidirectional"))
    )
    (net (code "213") (name "unconnected-(U2A-PB5-Pad57)") (class "Default")
      (node (ref "U2") (pin "57") (pinfunction "PB5_57") (pintype "bidirectional"))
    )
    (net (code "214") (name "unconnected-(U2A-PB8-Pad61)") (class "Default")
      (node (ref "U2") (pin "61") (pinfunction "PB8_61") (pintype "bidirectional"))
    )
    (net (code "215") (name "unconnected-(U2A-PB9-Pad62)") (class "Default")
      (node (ref "U2") (pin "62") (pinfunction "PB9_62") (pintype "bidirectional"))
    )
    (net (code "216") (name "unconnected-(U2A-PB12-Pad33)") (class "Default")
      (node (ref "U2") (pin "33") (pinfunction "PB12_33") (pintype "bidirectional"))
    )
    (net (code "217") (name "unconnected-(U2A-PC6-Pad37)") (class "Default")
      (node (ref "U2") (pin "37") (pinfunction "PC6_37") (pintype "bidirectional"))
    )
    (net (code "218") (name "unconnected-(U2A-PC7-Pad38)") (class "Default")
      (node (ref "U2") (pin "38") (pinfunction "PC7_38") (pintype "bidirectional"))
    )
    (net (code "219") (name "unconnected-(U2A-PC8-Pad39)") (class "Default")
      (node (ref "U2") (pin "39") (pinfunction "PC8_39") (pintype "bidirectional"))
    )
    (net (code "220") (name "unconnected-(U2A-PC9-Pad40)") (class "Default")
      (node (ref "U2") (pin "40") (pinfunction "PC9_40") (pintype "bidirectional"))
    )
    (net (code "221") (name "unconnected-(U2A-PC13-TAMPER-RTC-Pad2)") (class "Default")
      (node (ref "U2") (pin "2") (pinfunction "PC13-TAMPER-RTC_2") (pintype "bidirectional"))
    )
    (net (code "222") (name "unconnected-(U3-P2.2{slash}A10{slash}MISO_2-Pad35)") (class "Default")
      (node (ref "U3") (pin "35") (pinfunction "P2.2/A10/MISO_2_35") (pintype "passive"))
    )
    (net (code "223") (name "unconnected-(U3-P2.3{slash}A11{slash}MOSI_2-Pad36)") (class "Default")
      (node (ref "U3") (pin "36") (pinfunction "P2.3/A11/MOSI_2_36") (pintype "passive"))
    )
    (net (code "224") (name "unconnected-(U3-P2.4{slash}A12{slash}ECI_3{slash}SS_2-Pad37)") (class "Default")
      (node (ref "U3") (pin "37") (pinfunction "P2.4/A12/ECI_3/SS_2_37") (pintype "passive"))
    )
    (net (code "225") (name "unconnected-(U3-P2.5{slash}A13{slash}CCP0_3-Pad38)") (class "Default")
      (node (ref "U3") (pin "38") (pinfunction "P2.5/A13/CCP0_3_38") (pintype "passive"))
    )
    (net (code "226") (name "unconnected-(U3-P2.6{slash}A14{slash}CCP1_3-Pad39)") (class "Default")
      (node (ref "U3") (pin "39") (pinfunction "P2.6/A14/CCP1_3_39") (pintype "passive"))
    )
    (net (code "227") (name "unconnected-(U3-P3.3{slash}INT1-Pad22)") (class "Default")
      (node (ref "U3") (pin "22") (pinfunction "P3.3/INT1_22") (pintype "passive+no_connect"))
    )
    (net (code "228") (name "unconnected-(U3-P3.4{slash}T0{slash}T1CLKO{slash}ECI_2-Pad23)") (class "Default")
      (node (ref "U3") (pin "23") (pinfunction "P3.4/T0/T1CLKO/ECI_2_23") (pintype "passive+no_connect"))
    )
    (net (code "229") (name "unconnected-(U3-P3.5{slash}T1{slash}T0CLKO{slash}CCP0_2-Pad26)") (class "Default")
      (node (ref "U3") (pin "26") (pinfunction "P3.5/T1/T0CLKO/CCP0_2_26") (pintype "passive+no_connect"))
    )
    (net (code "230") (name "unconnected-(U3-P4.0{slash}MOSI_3-Pad18)") (class "Default")
      (node (ref "U3") (pin "18") (pinfunction "P4.0/MOSI_3_18") (pintype "passive+no_connect"))
    )
    (net (code "231") (name "unconnected-(U3-P5.5{slash}CMP+-Pad16)") (class "Default")
      (node (ref "U3") (pin "16") (pinfunction "P5.5/CMP+_16") (pintype "passive+no_connect"))
    )
    (net (code "232") (name "unconnected-(U4-CTS-Pad3)") (class "Default")
      (node (ref "U4") (pin "3") (pinfunction "CTS_3") (pintype "passive"))
    )
    (net (code "233") (name "unconnected-(U4-ETH-Pad13)") (class "Default")
      (node (ref "U4") (pin "13") (pinfunction "ETH_13") (pintype "passive"))
    )
    (net (code "234") (name "unconnected-(U4-ETH-Pad14)") (class "Default")
      (node (ref "U4") (pin "14") (pinfunction "ETH_14") (pintype "passive"))
    )
    (net (code "235") (name "unconnected-(U4-LED_DATA-Pad7)") (class "Default")
      (node (ref "U4") (pin "7") (pinfunction "LED_DATA_7") (pintype "passive"))
    )
    (net (code "236") (name "unconnected-(U4-NC-Pad1)") (class "Default")
      (node (ref "U4") (pin "1") (pinfunction "NC_1") (pintype "passive"))
    )
    (net (code "237") (name "unconnected-(U4-NC-Pad2)") (class "Default")
      (node (ref "U4") (pin "2") (pinfunction "NC_2") (pintype "passive"))
    )
    (net (code "238") (name "unconnected-(U4-RESET-Pad4)") (class "Default")
      (node (ref "U4") (pin "4") (pinfunction "RESET_4") (pintype "passive"))
    )
    (net (code "239") (name "unconnected-(U4-RST-Pad5)") (class "Default")
      (node (ref "U4") (pin "5") (pinfunction "RST_5") (pintype "passive"))
    )
    (net (code "240") (name "unconnected-(U4-Reload-Pad6)") (class "Default")
      (node (ref "U4") (pin "6") (pinfunction "Reload_6") (pintype "passive"))
    )
  )
)
